# clone_Schematics.net
KiCad netlist of a schematic drawn in Altium Designer
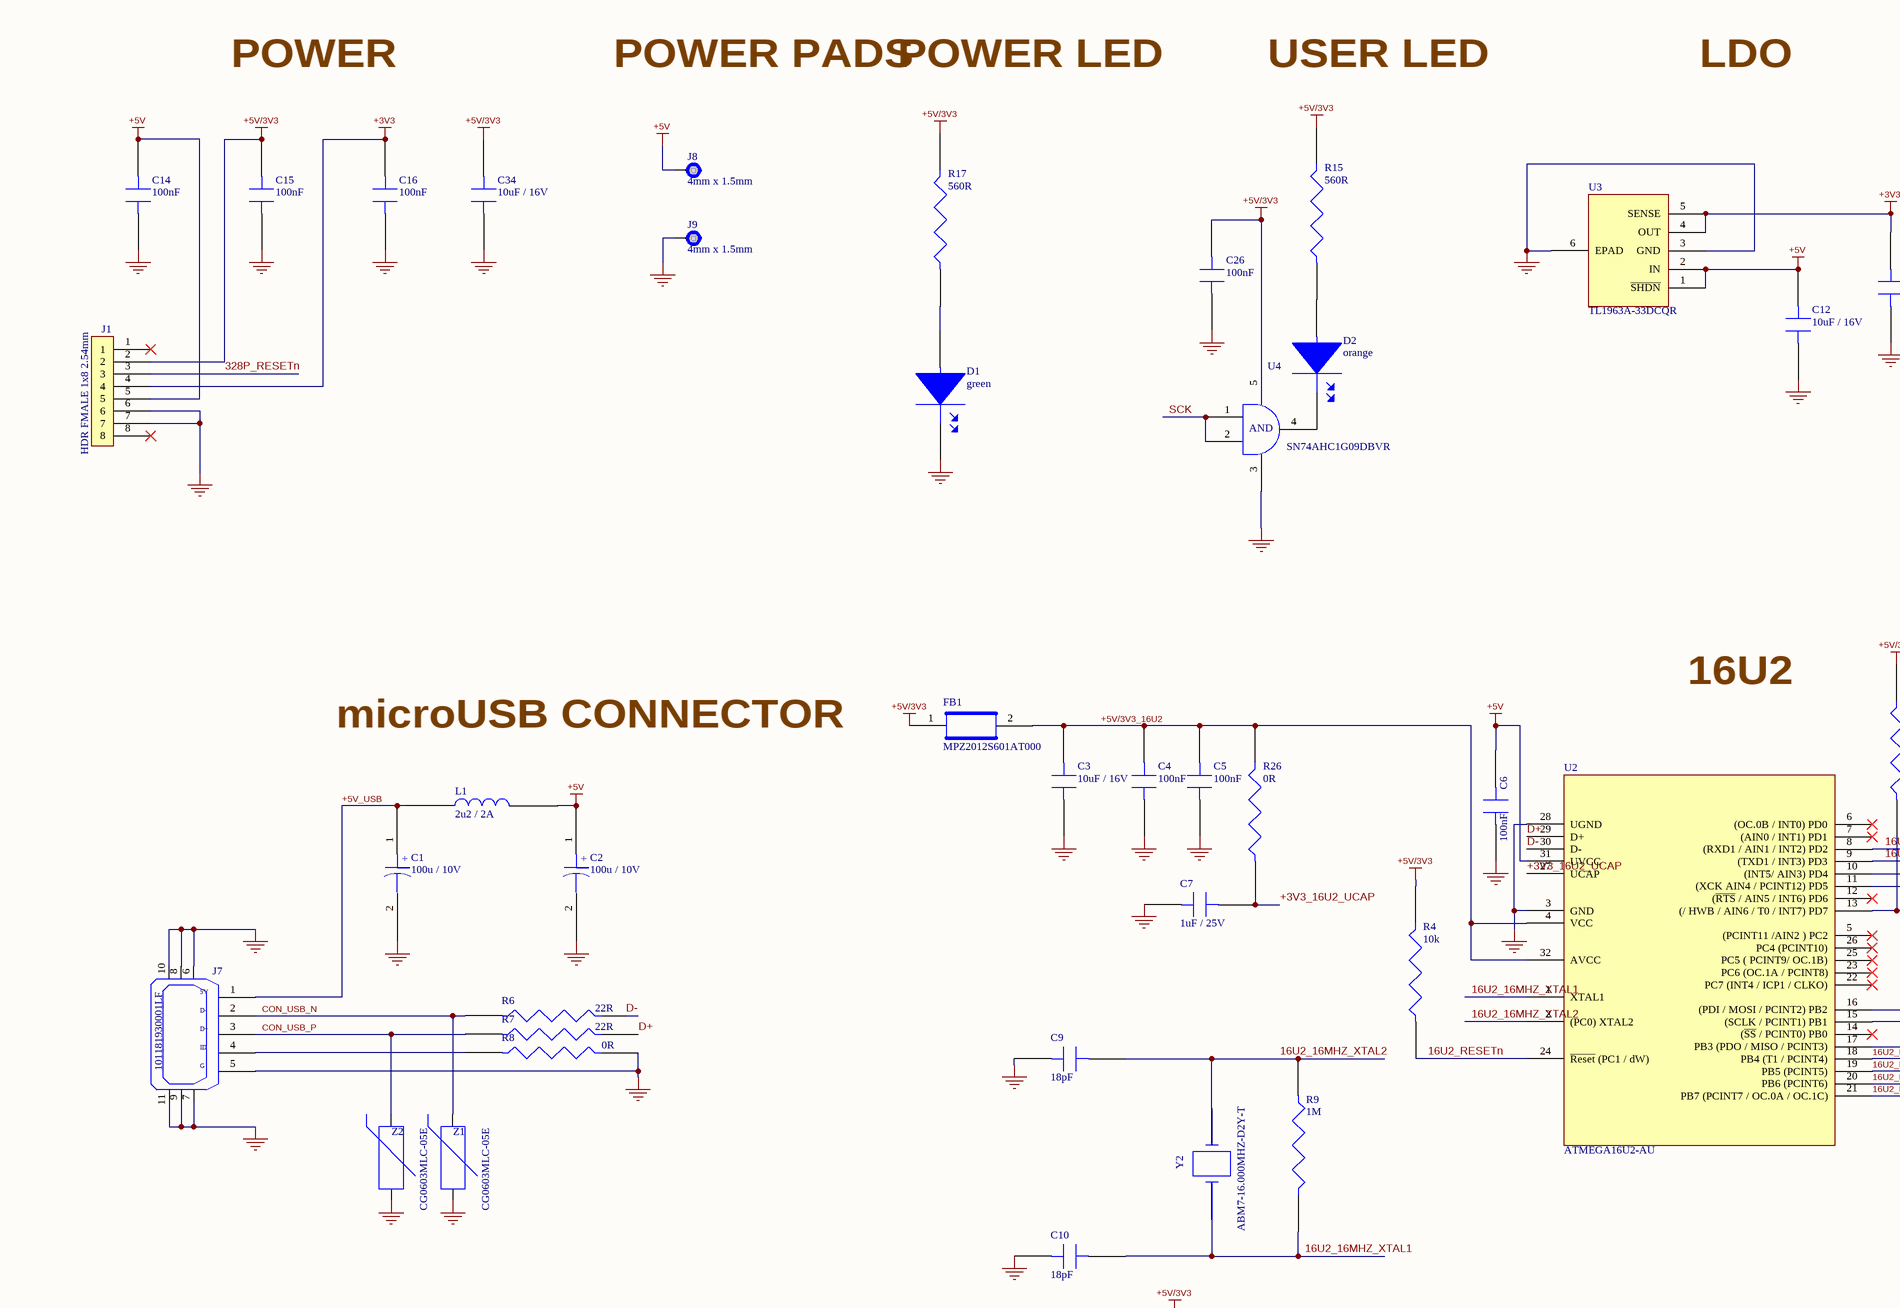
[diagram p0: clone_Schematics.SchDoc, top left]
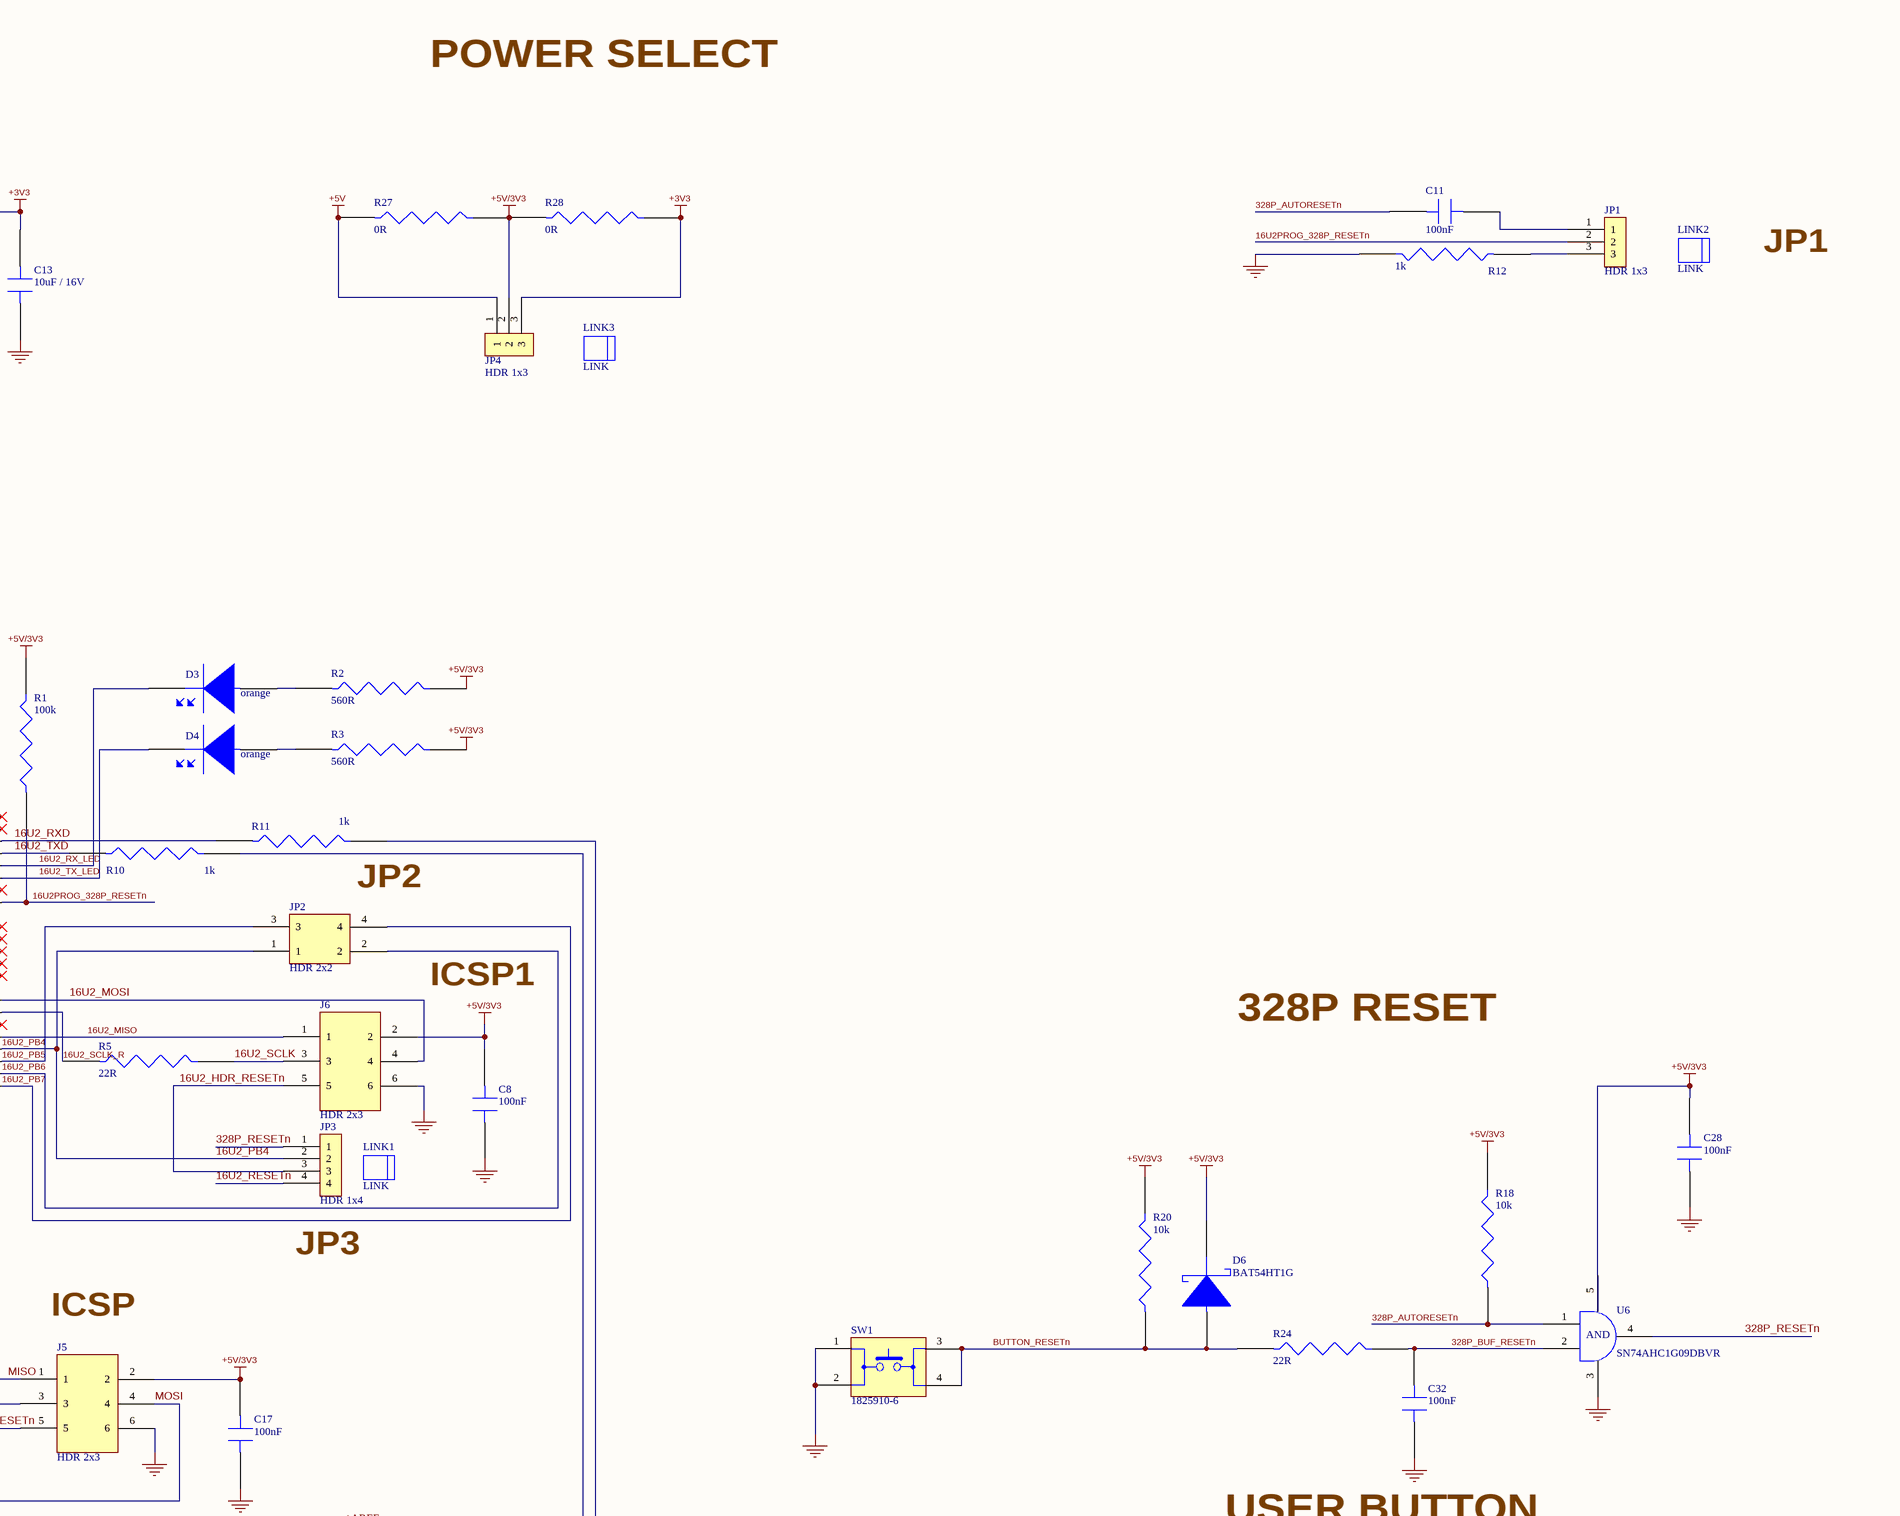
[diagram p1: clone_Schematics.SchDoc, top right]
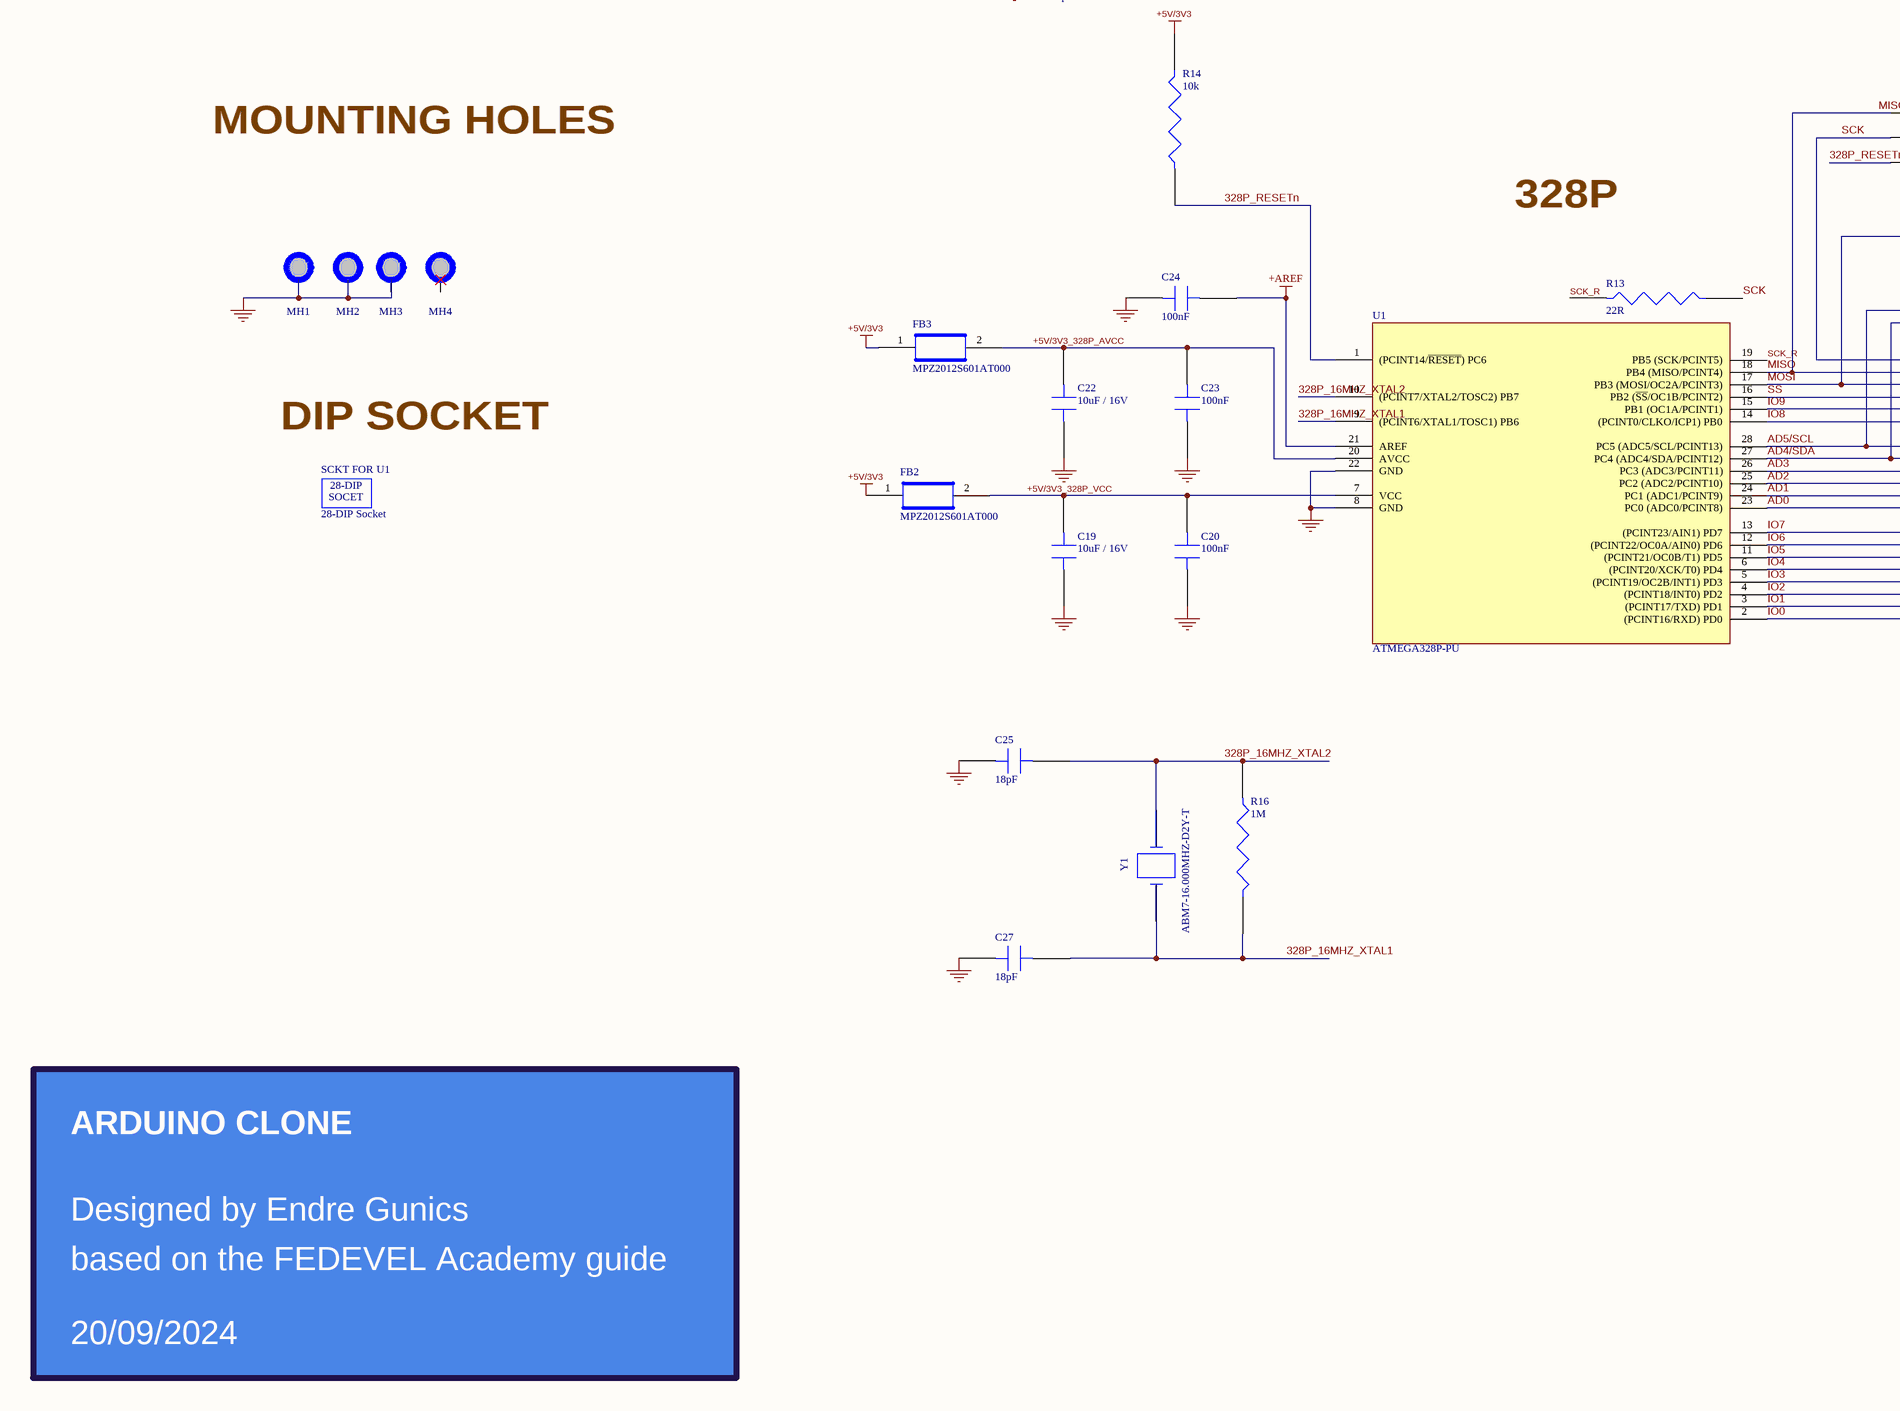
[diagram p2: clone_Schematics.SchDoc, bottom left]
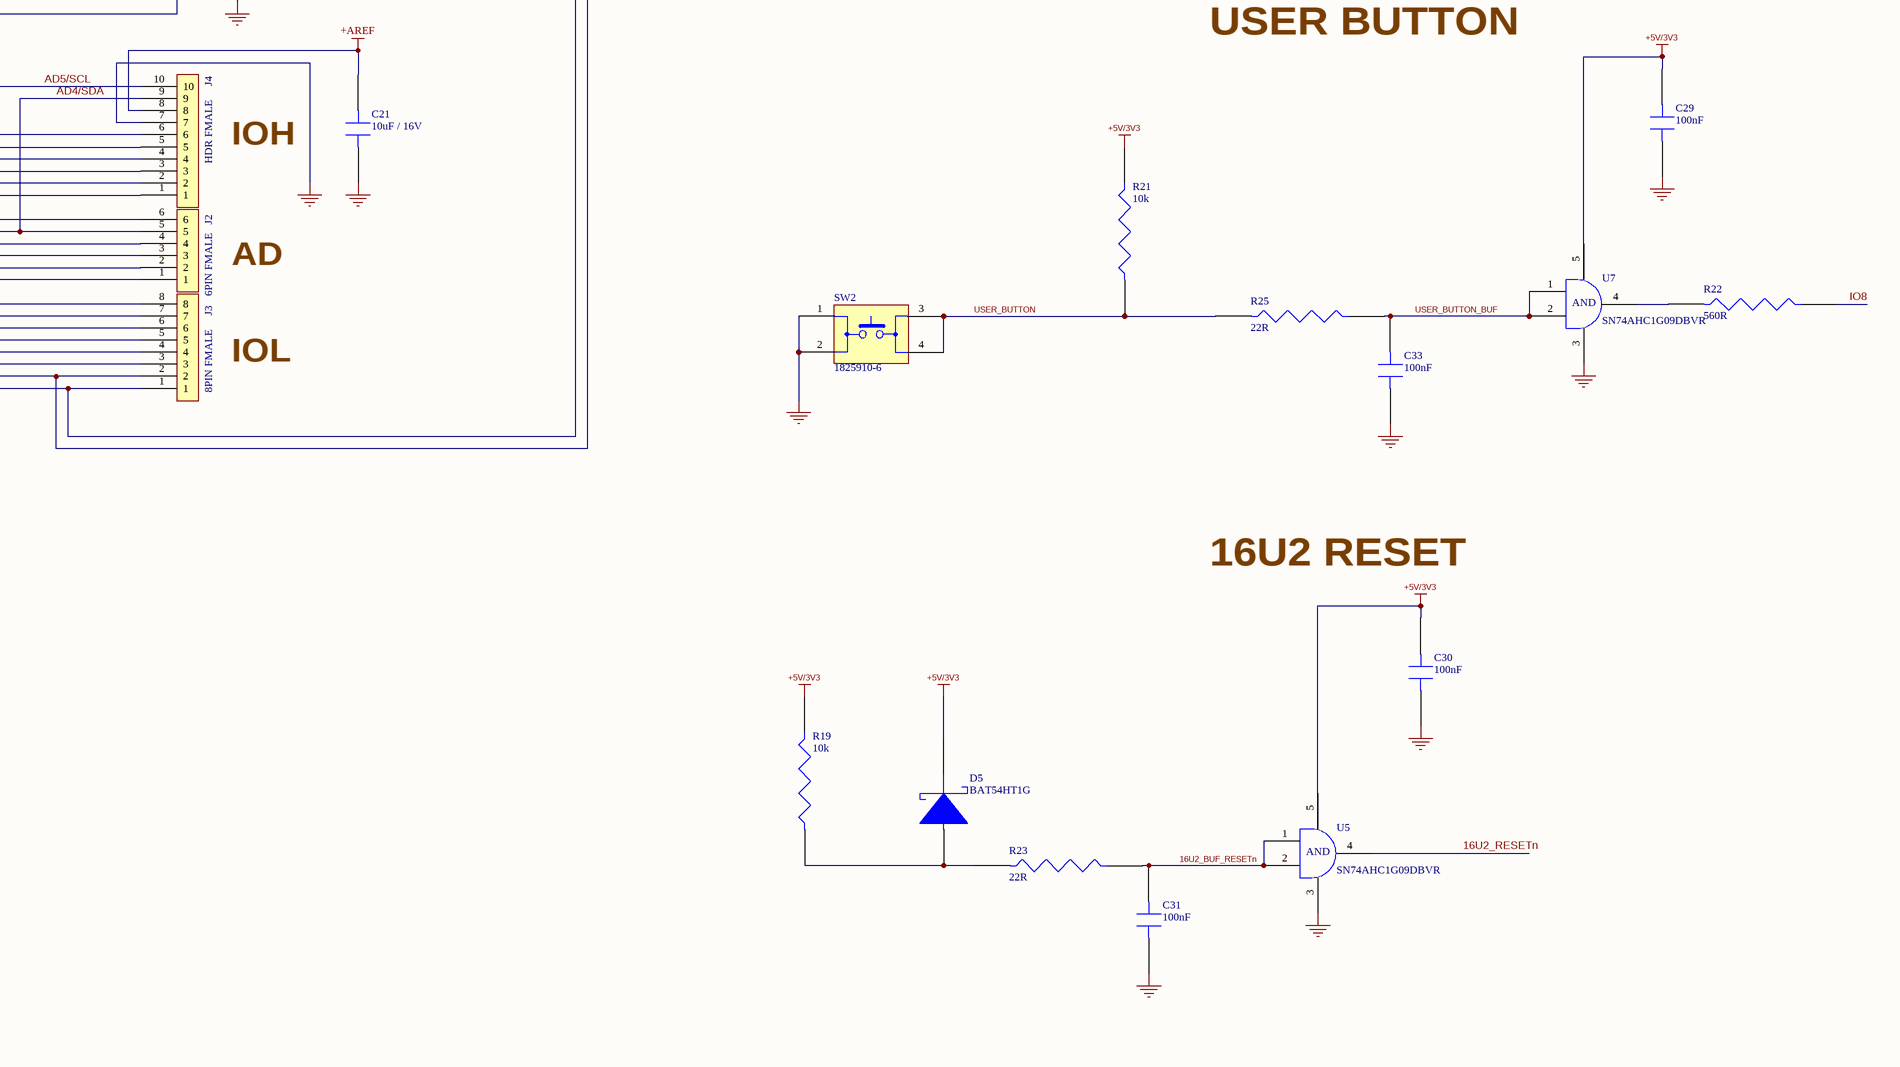
[diagram p3: clone_Schematics.SchDoc, bottom right]

(export (version "E")
  (design (tool "Eeschema 10.0.6"))
  (components
    (comp (ref "C1")
      (value "100u / 10V")
      (footprint "C_ALU")
      (description "Aluminum Electrolytic Capacitor, 100 uF, 10 V, ± 20%, 1000 hours @ 85°C, Radial Can - SMD")
      (fields
        (field (name "MANUFACTURER") "Panasonic")
        (field (name "MANUFACTURER PART NUMBER") "EEE-1AA101WR")
      )
      (libsource (lib "clone_Schematic_libary") (part "EEE-1AA101WR"))
    )
    (comp (ref "C2")
      (value "100u / 10V")
      (footprint "C_ALU")
      (description "Aluminum Electrolytic Capacitor, 100 uF, 10 V, ± 20%, 1000 hours @ 85°C, Radial Can - SMD")
      (fields
        (field (name "MANUFACTURER") "Panasonic")
        (field (name "MANUFACTURER PART NUMBER") "EEE-1AA101WR")
      )
      (libsource (lib "clone_Schematic_libary") (part "EEE-1AA101WR"))
    )
    (comp (ref "C3")
      (value "10uF / 16V")
      (footprint "C0805")
      (libsource (lib "clone_Schematic_libary") (part "CAP2"))
    )
    (comp (ref "C4")
      (value "100nF")
      (footprint "C0805")
      (description "Multilayer Ceramic Capacitor, 0.1 uF, 50 V, ± 10%, X7R, 0805 [2012 Metric]")
      (fields
        (field (name "MANUFACTURER") "TDK")
        (field (name "MANUFACTURER PART NUMBER") "C2012X7R1H104K085AA")
      )
      (libsource (lib "clone_Schematic_libary") (part "C2012X7R1H104K085AA"))
    )
    (comp (ref "C5")
      (value "100nF")
      (footprint "C0805")
      (description "Multilayer Ceramic Capacitor, 0.1 uF, 50 V, ± 10%, X7R, 0805 [2012 Metric]")
      (fields
        (field (name "MANUFACTURER") "TDK")
        (field (name "MANUFACTURER PART NUMBER") "C2012X7R1H104K085AA")
      )
      (libsource (lib "clone_Schematic_libary") (part "C2012X7R1H104K085AA"))
    )
    (comp (ref "C6")
      (value "100nF")
      (footprint "C0805")
      (description "Multilayer Ceramic Capacitor, 0.1 uF, 50 V, ± 10%, X7R, 0805 [2012 Metric]")
      (fields
        (field (name "MANUFACTURER") "TDK")
        (field (name "MANUFACTURER PART NUMBER") "C2012X7R1H104K085AA")
      )
      (libsource (lib "clone_Schematic_libary") (part "C2012X7R1H104K085AA"))
    )
    (comp (ref "C7")
      (value "1uF / 25V")
      (footprint "C0805")
      (description "CAP CER 1UF 25V X5R 0805")
      (fields
        (field (name "MANUFACTURER") "TDK")
        (field (name "MANUFACTURER PART NUMBER") "C2012X5R1E105K125AA")
      )
      (libsource (lib "clone_Schematic_libary") (part "C2012X5R1E105K125AA"))
    )
    (comp (ref "C8")
      (value "100nF")
      (footprint "C0805")
      (description "Multilayer Ceramic Capacitor, 0.1 uF, 50 V, ± 10%, X7R, 0805 [2012 Metric]")
      (fields
        (field (name "MANUFACTURER") "TDK")
        (field (name "MANUFACTURER PART NUMBER") "C2012X7R1H104K085AA")
      )
      (libsource (lib "clone_Schematic_libary") (part "C2012X7R1H104K085AA"))
    )
    (comp (ref "C9")
      (value "18pF")
      (footprint "C0805")
      (description "Cap Cer 0805 18PF 50VDC X8G 5%")
      (fields
        (field (name "MANUFACTURER") "KEMET")
        (field (name "MANUFACTURER PART NUMBER") "C0805C180J5TACTU")
      )
      (libsource (lib "clone_Schematic_libary") (part "C0805C180J5TACTU"))
    )
    (comp (ref "C10")
      (value "18pF")
      (footprint "C0805")
      (description "Cap Cer 0805 18PF 50VDC X8G 5%")
      (fields
        (field (name "MANUFACTURER") "KEMET")
        (field (name "MANUFACTURER PART NUMBER") "C0805C180J5TACTU")
      )
      (libsource (lib "clone_Schematic_libary") (part "C0805C180J5TACTU"))
    )
    (comp (ref "C11")
      (value "100nF")
      (footprint "C0805")
      (description "Multilayer Ceramic Capacitor, 0.1 uF, 50 V, ± 10%, X7R, 0805 [2012 Metric]")
      (fields
        (field (name "MANUFACTURER") "TDK")
        (field (name "MANUFACTURER PART NUMBER") "C2012X7R1H104K085AA")
      )
      (libsource (lib "clone_Schematic_libary") (part "C2012X7R1H104K085AA"))
    )
    (comp (ref "C12")
      (value "10uF / 16V")
      (footprint "C0805")
      (libsource (lib "clone_Schematic_libary") (part "CAP2"))
    )
    (comp (ref "C13")
      (value "10uF / 16V")
      (footprint "C0805")
      (libsource (lib "clone_Schematic_libary") (part "CAP2"))
    )
    (comp (ref "C14")
      (value "100nF")
      (footprint "C0805")
      (description "Multilayer Ceramic Capacitor, 0.1 uF, 50 V, ± 10%, X7R, 0805 [2012 Metric]")
      (fields
        (field (name "MANUFACTURER") "TDK")
        (field (name "MANUFACTURER PART NUMBER") "C2012X7R1H104K085AA")
      )
      (libsource (lib "clone_Schematic_libary") (part "C2012X7R1H104K085AA"))
    )
    (comp (ref "C15")
      (value "100nF")
      (footprint "C0805")
      (description "Multilayer Ceramic Capacitor, 0.1 uF, 50 V, ± 10%, X7R, 0805 [2012 Metric]")
      (fields
        (field (name "MANUFACTURER") "TDK")
        (field (name "MANUFACTURER PART NUMBER") "C2012X7R1H104K085AA")
      )
      (libsource (lib "clone_Schematic_libary") (part "C2012X7R1H104K085AA"))
    )
    (comp (ref "C16")
      (value "100nF")
      (footprint "C0805")
      (description "Multilayer Ceramic Capacitor, 0.1 uF, 50 V, ± 10%, X7R, 0805 [2012 Metric]")
      (fields
        (field (name "MANUFACTURER") "TDK")
        (field (name "MANUFACTURER PART NUMBER") "C2012X7R1H104K085AA")
      )
      (libsource (lib "clone_Schematic_libary") (part "C2012X7R1H104K085AA"))
    )
    (comp (ref "C17")
      (value "100nF")
      (footprint "C0805")
      (description "Multilayer Ceramic Capacitor, 0.1 uF, 50 V, ± 10%, X7R, 0805 [2012 Metric]")
      (fields
        (field (name "MANUFACTURER") "TDK")
        (field (name "MANUFACTURER PART NUMBER") "C2012X7R1H104K085AA")
      )
      (libsource (lib "clone_Schematic_libary") (part "C2012X7R1H104K085AA"))
    )
    (comp (ref "C19")
      (value "10uF / 16V")
      (footprint "C0805")
      (libsource (lib "clone_Schematic_libary") (part "CAP2"))
    )
    (comp (ref "C20")
      (value "100nF")
      (footprint "C0805")
      (description "Multilayer Ceramic Capacitor, 0.1 uF, 50 V, ± 10%, X7R, 0805 [2012 Metric]")
      (fields
        (field (name "MANUFACTURER") "TDK")
        (field (name "MANUFACTURER PART NUMBER") "C2012X7R1H104K085AA")
      )
      (libsource (lib "clone_Schematic_libary") (part "C2012X7R1H104K085AA"))
    )
    (comp (ref "C21")
      (value "10uF / 16V")
      (footprint "C0805")
      (libsource (lib "clone_Schematic_libary") (part "CAP2"))
    )
    (comp (ref "C22")
      (value "10uF / 16V")
      (footprint "C0805")
      (libsource (lib "clone_Schematic_libary") (part "CAP2"))
    )
    (comp (ref "C23")
      (value "100nF")
      (footprint "C0805")
      (description "Multilayer Ceramic Capacitor, 0.1 uF, 50 V, ± 10%, X7R, 0805 [2012 Metric]")
      (fields
        (field (name "MANUFACTURER") "TDK")
        (field (name "MANUFACTURER PART NUMBER") "C2012X7R1H104K085AA")
      )
      (libsource (lib "clone_Schematic_libary") (part "C2012X7R1H104K085AA"))
    )
    (comp (ref "C24")
      (value "100nF")
      (footprint "C0805")
      (description "Multilayer Ceramic Capacitor, 0.1 uF, 50 V, ± 10%, X7R, 0805 [2012 Metric]")
      (fields
        (field (name "MANUFACTURER") "TDK")
        (field (name "MANUFACTURER PART NUMBER") "C2012X7R1H104K085AA")
      )
      (libsource (lib "clone_Schematic_libary") (part "C2012X7R1H104K085AA"))
    )
    (comp (ref "C25")
      (value "18pF")
      (footprint "C0805")
      (description "Cap Cer 0805 18PF 50VDC X8G 5%")
      (fields
        (field (name "MANUFACTURER") "KEMET")
        (field (name "MANUFACTURER PART NUMBER") "C0805C180J5TACTU")
      )
      (libsource (lib "clone_Schematic_libary") (part "C0805C180J5TACTU"))
    )
    (comp (ref "C26")
      (value "100nF")
      (footprint "C0805")
      (description "Multilayer Ceramic Capacitor, 0.1 uF, 50 V, ± 10%, X7R, 0805 [2012 Metric]")
      (fields
        (field (name "MANUFACTURER") "TDK")
        (field (name "MANUFACTURER PART NUMBER") "C2012X7R1H104K085AA")
      )
      (libsource (lib "clone_Schematic_libary") (part "C2012X7R1H104K085AA"))
    )
    (comp (ref "C27")
      (value "18pF")
      (footprint "C0805")
      (description "Cap Cer 0805 18PF 50VDC X8G 5%")
      (fields
        (field (name "MANUFACTURER") "KEMET")
        (field (name "MANUFACTURER PART NUMBER") "C0805C180J5TACTU")
      )
      (libsource (lib "clone_Schematic_libary") (part "C0805C180J5TACTU"))
    )
    (comp (ref "C28")
      (value "100nF")
      (footprint "C0805")
      (description "Multilayer Ceramic Capacitor, 0.1 uF, 50 V, ± 10%, X7R, 0805 [2012 Metric]")
      (fields
        (field (name "MANUFACTURER") "TDK")
        (field (name "MANUFACTURER PART NUMBER") "C2012X7R1H104K085AA")
      )
      (libsource (lib "clone_Schematic_libary") (part "C2012X7R1H104K085AA"))
    )
    (comp (ref "C29")
      (value "100nF")
      (footprint "C0805")
      (description "Multilayer Ceramic Capacitor, 0.1 uF, 50 V, ± 10%, X7R, 0805 [2012 Metric]")
      (fields
        (field (name "MANUFACTURER") "TDK")
        (field (name "MANUFACTURER PART NUMBER") "C2012X7R1H104K085AA")
      )
      (libsource (lib "clone_Schematic_libary") (part "C2012X7R1H104K085AA"))
    )
    (comp (ref "C30")
      (value "100nF")
      (footprint "C0805")
      (description "Multilayer Ceramic Capacitor, 0.1 uF, 50 V, ± 10%, X7R, 0805 [2012 Metric]")
      (fields
        (field (name "MANUFACTURER") "TDK")
        (field (name "MANUFACTURER PART NUMBER") "C2012X7R1H104K085AA")
      )
      (libsource (lib "clone_Schematic_libary") (part "C2012X7R1H104K085AA"))
    )
    (comp (ref "C31")
      (value "100nF")
      (footprint "C0805")
      (description "Multilayer Ceramic Capacitor, 0.1 uF, 50 V, ± 10%, X7R, 0805 [2012 Metric]")
      (fields
        (field (name "MANUFACTURER") "TDK")
        (field (name "MANUFACTURER PART NUMBER") "C2012X7R1H104K085AA")
      )
      (libsource (lib "clone_Schematic_libary") (part "C2012X7R1H104K085AA"))
    )
    (comp (ref "C32")
      (value "100nF")
      (footprint "C0805")
      (description "Multilayer Ceramic Capacitor, 0.1 uF, 50 V, ± 10%, X7R, 0805 [2012 Metric]")
      (fields
        (field (name "MANUFACTURER") "TDK")
        (field (name "MANUFACTURER PART NUMBER") "C2012X7R1H104K085AA")
      )
      (libsource (lib "clone_Schematic_libary") (part "C2012X7R1H104K085AA"))
    )
    (comp (ref "C33")
      (value "100nF")
      (footprint "C0805")
      (description "Multilayer Ceramic Capacitor, 0.1 uF, 50 V, ± 10%, X7R, 0805 [2012 Metric]")
      (fields
        (field (name "MANUFACTURER") "TDK")
        (field (name "MANUFACTURER PART NUMBER") "C2012X7R1H104K085AA")
      )
      (libsource (lib "clone_Schematic_libary") (part "C2012X7R1H104K085AA"))
    )
    (comp (ref "C34")
      (value "10uF / 16V")
      (footprint "C0805")
      (libsource (lib "clone_Schematic_libary") (part "CAP2"))
    )
    (comp (ref "D1")
      (value "green")
      (footprint "orangeDiode")
      (description "LED Uni-Color Green 572nm Automotive 2-Pin Chip 0603(1608Metric) T/R")
      (fields
        (field (name "MANUFACTURER") "Osram Opto")
        (field (name "MANUFACTURER PART NUMBER") "LGL29K-G2J1-24-Z")
      )
      (libsource (lib "clone_Schematic_libary") (part "LGL29K-G2J1-24-Z"))
    )
    (comp (ref "D2")
      (value "orange")
      (footprint "orangeDiode")
      (libsource (lib "clone_Schematic_libary") (part "LED"))
    )
    (comp (ref "D3")
      (value "orange")
      (footprint "orangeDiode")
      (libsource (lib "clone_Schematic_libary") (part "LED"))
    )
    (comp (ref "D4")
      (value "orange")
      (footprint "orangeDiode")
      (libsource (lib "clone_Schematic_libary") (part "LED"))
    )
    (comp (ref "D5")
      (value "BAT54HT1G")
      (footprint "SOD323")
      (description "Small Signal Schottky Diode, Single, 30 V, 200 Ma, 800 Mv, 600 Ma, 150 C")
      (fields (field (name "MANUFACTURER") "ON Semiconductor / Fairchild"))
      (libsource (lib "clone_Schematic_libary") (part "BAT54HT1G"))
    )
    (comp (ref "D6")
      (value "BAT54HT1G")
      (footprint "SOD323")
      (description "Small Signal Schottky Diode, Single, 30 V, 200 Ma, 800 Mv, 600 Ma, 150 C")
      (fields (field (name "MANUFACTURER") "ON Semiconductor / Fairchild"))
      (libsource (lib "clone_Schematic_libary") (part "BAT54HT1G"))
    )
    (comp (ref "FB1")
      (value "MPZ2012S601AT000")
      (footprint "C0805")
      (description "Ferrite Beads Multi-Layer Power 600Ohm 25% 100MHz 2A 100mOhm DCR 0805 T/R")
      (fields (field (name "MANUFACTURER") "TDK") (field (name "TOLERANCE") "25%"))
      (libsource (lib "clone_Schematic_libary") (part "MPZ2012S601AT000"))
    )
    (comp (ref "FB2")
      (value "MPZ2012S601AT000")
      (footprint "C0805")
      (description "Ferrite Beads Multi-Layer Power 600Ohm 25% 100MHz 2A 100mOhm DCR 0805 T/R")
      (fields (field (name "MANUFACTURER") "TDK") (field (name "TOLERANCE") "25%"))
      (libsource (lib "clone_Schematic_libary") (part "MPZ2012S601AT000"))
    )
    (comp (ref "FB3")
      (value "MPZ2012S601AT000")
      (footprint "C0805")
      (description "Ferrite Beads Multi-Layer Power 600Ohm 25% 100MHz 2A 100mOhm DCR 0805 T/R")
      (fields (field (name "MANUFACTURER") "TDK") (field (name "TOLERANCE") "25%"))
      (libsource (lib "clone_Schematic_libary") (part "MPZ2012S601AT000"))
    )
    (comp (ref "J1")
      (value "HDR FMALE 1x8 2.54mm")
      (footprint "8PINFMALE")
      (libsource (lib "clone_Schematic_libary") (part "8PIN"))
    )
    (comp (ref "J2")
      (value "6PIN FMALE")
      (footprint "6PINFMALE")
      (libsource (lib "clone_Schematic_libary") (part "6PIN"))
    )
    (comp (ref "J3") (value "8PIN FMALE") (footprint "8PINFMALE") (libsource (lib "") (part "8PIN_1")))
    (comp (ref "J4")
      (value "HDR FMALE")
      (footprint "10PINFMALE")
      (libsource (lib "clone_Schematic_libary") (part "10PIN"))
    )
    (comp (ref "J5")
      (value "HDR 2x3")
      (footprint "HDR 2x3")
      (description "Conn Unshrouded Header HDR 6 POS 2.54mm Solder ST Top Entry Thru-Hole BergStik® Bulk")
      (fields
        (field (name "MANUFACTURER") "Amphenol ICC / FCI")
        (field (name "MANUFACTURER PART NUMBER") "67997-106HLF")
      )
      (libsource (lib "clone_Schematic_libary") (part "67997-106HLF"))
    )
    (comp (ref "J6")
      (value "HDR 2x3")
      (footprint "HDR 2x3")
      (description "Conn Unshrouded Header HDR 6 POS 2.54mm Solder ST Top Entry Thru-Hole BergStik® Bulk")
      (fields
        (field (name "MANUFACTURER") "Amphenol ICC / FCI")
        (field (name "MANUFACTURER PART NUMBER") "67997-106HLF")
      )
      (libsource (lib "clone_Schematic_libary") (part "67997-106HLF"))
    )
    (comp (ref "J7")
      (value "101181930001LF")
      (footprint "USBmicro")
      (description "MICRO USB B0TYPE F-10118193-0001LF ¦ Amphenol FCI (Amphenol CS) 101181930001LF")
      (fields (field (name "MANUFACTURER") "Amphenol Communications Solutions"))
      (libsource (lib "clone_Schematic_libary") (part "101181930001LF"))
    )
    (comp (ref "J8")
      (value "4mm x 1.5mm")
      (footprint "PAD WITH HOLE")
      (description "pad with hole")
      (libsource (lib "clone_Schematic_libary") (part "PAD_WITH_HOLE"))
    )
    (comp (ref "J9")
      (value "4mm x 1.5mm")
      (footprint "PAD WITH HOLE")
      (description "pad with hole")
      (libsource (lib "clone_Schematic_libary") (part "PAD_WITH_HOLE"))
    )
    (comp (ref "JP1")
      (value "HDR 1x3")
      (footprint "HDR 1x3")
      (description "Conn Unshrouded Header HDR 3 POS 2.54mm Solder ST Top Entry Thru-Hole BergStik® Automotive Bulk")
      (fields
        (field (name "MANUFACTURER") "Amphenol ICC / FCI")
        (field (name "MANUFACTURER PART NUMBER") "68000-103HLF")
      )
      (libsource (lib "") (part "68000-103HLF_1"))
    )
    (comp (ref "JP2")
      (value "HDR 2x2")
      (footprint "HDR 2x2")
      (description "Conn Unshrouded Header HDR 4 POS 2.54mm Solder ST Top Entry Thru-Hole BergStik® Bulk")
      (fields
        (field (name "MANUFACTURER") "Amphenol ICC / FCI")
        (field (name "MANUFACTURER PART NUMBER") "68602-204HLF")
      )
      (libsource (lib "clone_Schematic_libary") (part "68602-204HLF"))
    )
    (comp (ref "JP3")
      (value "HDR 1x4")
      (footprint "HDR 1x4")
      (description "Conn Unshrouded Header HDR 4 POS 2.54mm Solder ST Thru-Hole Bag")
      (fields
        (field (name "MANUFACTURER") "Amphenol ICC / FCI")
        (field (name "MANUFACTURER PART NUMBER") "68001-204HLF")
      )
      (libsource (lib "clone_Schematic_libary") (part "68001-204HLF"))
    )
    (comp (ref "JP4")
      (value "HDR 1x3")
      (footprint "HDR 1x3")
      (description "Conn Unshrouded Header HDR 3 POS 2.54mm Solder ST Top Entry Thru-Hole BergStik® Automotive Bulk")
      (fields
        (field (name "MANUFACTURER") "Amphenol ICC / FCI")
        (field (name "MANUFACTURER PART NUMBER") "68000-103HLF")
      )
      (libsource (lib "clone_Schematic_libary") (part "68000-103HLF"))
    )
    (comp (ref "L1")
      (value "2u2 / 2A")
      (footprint "InductorC120")
      (libsource (lib "clone_Schematic_libary") (part "inductor"))
    )
    (comp (ref "LINK1")
      (value "LINK")
      (description "2 Position 2.54 mm Centerline Single Circuit Open Top Jumper")
      (fields
        (field (name "MANUFACTURER") "Sullins")
        (field (name "MANUFACTURER PART NUMBER") "QPC02SXGN-RC")
      )
      (libsource (lib "clone_Schematic_libary") (part "QPC02SXGN-RC"))
    )
    (comp (ref "LINK2")
      (value "LINK")
      (description "2 Position 2.54 mm Centerline Single Circuit Open Top Jumper")
      (fields
        (field (name "MANUFACTURER") "Sullins")
        (field (name "MANUFACTURER PART NUMBER") "QPC02SXGN-RC")
      )
      (libsource (lib "clone_Schematic_libary") (part "QPC02SXGN-RC"))
    )
    (comp (ref "LINK3")
      (value "LINK")
      (description "2 Position 2.54 mm Centerline Single Circuit Open Top Jumper")
      (fields
        (field (name "MANUFACTURER") "Sullins")
        (field (name "MANUFACTURER PART NUMBER") "QPC02SXGN-RC")
      )
      (libsource (lib "clone_Schematic_libary") (part "QPC02SXGN-RC"))
    )
    (comp (ref "MH1")
      (value "MH_7.4MMC_3.2mmD")
      (footprint "MH_7.4_MMD_3.2_MMD")
      (description "MH 7.4 mm Dia 3.2mm Drill")
      (libsource (lib "clone_Schematic_libary") (part "mounting hole 7.4mm C3.2"))
    )
    (comp (ref "MH2")
      (value "MH_7.4MMC_3.2mmD")
      (footprint "MH_7.4_MMD_3.2_MMD")
      (description "MH 7.4 mm Dia 3.2mm Drill")
      (libsource (lib "clone_Schematic_libary") (part "mounting hole 7.4mm C3.2"))
    )
    (comp (ref "MH3")
      (value "MH_7.4MMC_3.2mmD")
      (footprint "MH_7.4_MMD_3.2_MMD")
      (description "MH 7.4 mm Dia 3.2mm Drill")
      (libsource (lib "clone_Schematic_libary") (part "mounting hole 7.4mm C3.2"))
    )
    (comp (ref "MH4")
      (value "mounting hole nonplated")
      (footprint "MH_NOPLATE")
      (description "mounting hole nonplated 7.4x3.2 non copper")
      (libsource (lib "clone_Schematic_libary") (part "mounting hole nonplated"))
    )
    (comp (ref "R1")
      (value "100k")
      (footprint "R0805")
      (description "SMD Chip Resistor, 100 kOhm, ï¿½ 5%, 125 mW, 0805 [2012 Metric], Thick Film, General Purpose")
      (fields
        (field (name "MANUFACTURER") "Yageo")
        (field (name "MANUFACTURER PART NUMBER") "RC0805JR-07100KL")
      )
      (libsource (lib "clone_Schematic_libary") (part "RC0805JR-07100KL"))
    )
    (comp (ref "R2")
      (value "560R")
      (footprint "R0805")
      (description "Res General Purpose Thick Film 0805 560 Ohm 1% 1/8W ±100ppm/°C Molded Paper T/R")
      (fields
        (field (name "MANUFACTURER") "Yageo")
        (field (name "MANUFACTURER PART NUMBER") "RC0805FR-07560RL")
      )
      (libsource (lib "clone_Schematic_libary") (part "RC0805FR-07560RL"))
    )
    (comp (ref "R3")
      (value "560R")
      (footprint "R0805")
      (description "Res General Purpose Thick Film 0805 560 Ohm 1% 1/8W ±100ppm/°C Molded Paper T/R")
      (fields
        (field (name "MANUFACTURER") "Yageo")
        (field (name "MANUFACTURER PART NUMBER") "RC0805FR-07560RL")
      )
      (libsource (lib "clone_Schematic_libary") (part "RC0805FR-07560RL"))
    )
    (comp (ref "R4")
      (value "10k")
      (footprint "R0805")
      (description "SMD Chip Resistor, 10 kOhm, ï¿½ 1%, 125 mW, 0805 [2012 Metric], Thick Film, General Purpose")
      (fields
        (field (name "MANUFACTURER") "Yageo")
        (field (name "MANUFACTURER PART NUMBER") "RC0805FR-0710KL")
      )
      (libsource (lib "clone_Schematic_libary") (part "RC0805FR-0710KL"))
    )
    (comp (ref "R5")
      (value "22R")
      (footprint "R0805")
      (description "SMD Chip Resistor, 22 Ohm, ± 1%, 125 mW, 0805 [2012 Metric], Thick Film, General Purpose")
      (fields
        (field (name "MANUFACTURER") "Yageo")
        (field (name "MANUFACTURER PART NUMBER") "RC0805FR-0722RL")
      )
      (libsource (lib "clone_Schematic_libary") (part "RC0805FR-0722RL"))
    )
    (comp (ref "R6")
      (value "22R")
      (footprint "R0805")
      (description "SMD Chip Resistor, 22 Ohm, ± 1%, 125 mW, 0805 [2012 Metric], Thick Film, General Purpose")
      (fields
        (field (name "MANUFACTURER") "Yageo")
        (field (name "MANUFACTURER PART NUMBER") "RC0805FR-0722RL")
      )
      (libsource (lib "clone_Schematic_libary") (part "RC0805FR-0722RL"))
    )
    (comp (ref "R7")
      (value "22R")
      (footprint "R0805")
      (description "SMD Chip Resistor, 22 Ohm, ± 1%, 125 mW, 0805 [2012 Metric], Thick Film, General Purpose")
      (fields
        (field (name "MANUFACTURER") "Yageo")
        (field (name "MANUFACTURER PART NUMBER") "RC0805FR-0722RL")
      )
      (libsource (lib "clone_Schematic_libary") (part "RC0805FR-0722RL"))
    )
    (comp (ref "R8")
      (value "0R")
      (footprint "R0805")
      (libsource (lib "clone_Schematic_libary") (part "0Ohm Resistor"))
    )
    (comp (ref "R9")
      (value "1M")
      (footprint "R0805")
      (description "SMD Chip Resistor, 1 MOhm, ï¿½ 1%, 125 mW, 0805 [2012 Metric], Thick Film, General Purpose")
      (fields
        (field (name "MANUFACTURER") "Yageo")
        (field (name "MANUFACTURER PART NUMBER") "RC0805FR-071ML")
      )
      (libsource (lib "clone_Schematic_libary") (part "RC0805FR-071ML"))
    )
    (comp (ref "R10")
      (value "1k")
      (footprint "R0805")
      (description "SMD Chip Resistor, 1 kOhm, ï¿½ 1%, 125 mW, 0805 [2012 Metric], Thick Film, General Purpose")
      (fields
        (field (name "MANUFACTURER") "Yageo")
        (field (name "MANUFACTURER PART NUMBER") "RC0805FR-071KL")
      )
      (libsource (lib "clone_Schematic_libary") (part "RC0805FR-071KL"))
    )
    (comp (ref "R11")
      (value "1k")
      (footprint "R0805")
      (description "SMD Chip Resistor, 1 kOhm, ï¿½ 1%, 125 mW, 0805 [2012 Metric], Thick Film, General Purpose")
      (fields
        (field (name "MANUFACTURER") "Yageo")
        (field (name "MANUFACTURER PART NUMBER") "RC0805FR-071KL")
      )
      (libsource (lib "clone_Schematic_libary") (part "RC0805FR-071KL"))
    )
    (comp (ref "R12")
      (value "1k")
      (footprint "R0805")
      (description "SMD Chip Resistor, 1 kOhm, ï¿½ 1%, 125 mW, 0805 [2012 Metric], Thick Film, General Purpose")
      (fields
        (field (name "MANUFACTURER") "Yageo")
        (field (name "MANUFACTURER PART NUMBER") "RC0805FR-071KL")
      )
      (libsource (lib "clone_Schematic_libary") (part "RC0805FR-071KL"))
    )
    (comp (ref "R13")
      (value "22R")
      (footprint "R0805")
      (description "SMD Chip Resistor, 22 Ohm, ± 1%, 125 mW, 0805 [2012 Metric], Thick Film, General Purpose")
      (fields
        (field (name "MANUFACTURER") "Yageo")
        (field (name "MANUFACTURER PART NUMBER") "RC0805FR-0722RL")
      )
      (libsource (lib "clone_Schematic_libary") (part "RC0805FR-0722RL"))
    )
    (comp (ref "R14")
      (value "10k")
      (footprint "R0805")
      (description "SMD Chip Resistor, 10 kOhm, ï¿½ 1%, 125 mW, 0805 [2012 Metric], Thick Film, General Purpose")
      (fields
        (field (name "MANUFACTURER") "Yageo")
        (field (name "MANUFACTURER PART NUMBER") "RC0805FR-0710KL")
      )
      (libsource (lib "clone_Schematic_libary") (part "RC0805FR-0710KL"))
    )
    (comp (ref "R15")
      (value "560R")
      (footprint "R0805")
      (description "Res General Purpose Thick Film 0805 560 Ohm 1% 1/8W ±100ppm/°C Molded Paper T/R")
      (fields
        (field (name "MANUFACTURER") "Yageo")
        (field (name "MANUFACTURER PART NUMBER") "RC0805FR-07560RL")
      )
      (libsource (lib "clone_Schematic_libary") (part "RC0805FR-07560RL"))
    )
    (comp (ref "R16")
      (value "1M")
      (footprint "R0805")
      (description "SMD Chip Resistor, 1 MOhm, ï¿½ 1%, 125 mW, 0805 [2012 Metric], Thick Film, General Purpose")
      (fields
        (field (name "MANUFACTURER") "Yageo")
        (field (name "MANUFACTURER PART NUMBER") "RC0805FR-071ML")
      )
      (libsource (lib "clone_Schematic_libary") (part "RC0805FR-071ML"))
    )
    (comp (ref "R17")
      (value "560R")
      (footprint "R0805")
      (description "Res General Purpose Thick Film 0805 560 Ohm 1% 1/8W ±100ppm/°C Molded Paper T/R")
      (fields
        (field (name "MANUFACTURER") "Yageo")
        (field (name "MANUFACTURER PART NUMBER") "RC0805FR-07560RL")
      )
      (libsource (lib "clone_Schematic_libary") (part "RC0805FR-07560RL"))
    )
    (comp (ref "R18")
      (value "10k")
      (footprint "R0805")
      (description "SMD Chip Resistor, 10 kOhm, ï¿½ 1%, 125 mW, 0805 [2012 Metric], Thick Film, General Purpose")
      (fields
        (field (name "MANUFACTURER") "Yageo")
        (field (name "MANUFACTURER PART NUMBER") "RC0805FR-0710KL")
      )
      (libsource (lib "clone_Schematic_libary") (part "RC0805FR-0710KL"))
    )
    (comp (ref "R19")
      (value "10k")
      (footprint "R0805")
      (description "SMD Chip Resistor, 10 kOhm, ï¿½ 1%, 125 mW, 0805 [2012 Metric], Thick Film, General Purpose")
      (fields
        (field (name "MANUFACTURER") "Yageo")
        (field (name "MANUFACTURER PART NUMBER") "RC0805FR-0710KL")
      )
      (libsource (lib "clone_Schematic_libary") (part "RC0805FR-0710KL"))
    )
    (comp (ref "R20")
      (value "10k")
      (footprint "R0805")
      (description "SMD Chip Resistor, 10 kOhm, ï¿½ 1%, 125 mW, 0805 [2012 Metric], Thick Film, General Purpose")
      (fields
        (field (name "MANUFACTURER") "Yageo")
        (field (name "MANUFACTURER PART NUMBER") "RC0805FR-0710KL")
      )
      (libsource (lib "clone_Schematic_libary") (part "RC0805FR-0710KL"))
    )
    (comp (ref "R21")
      (value "10k")
      (footprint "R0805")
      (description "SMD Chip Resistor, 10 kOhm, ï¿½ 1%, 125 mW, 0805 [2012 Metric], Thick Film, General Purpose")
      (fields
        (field (name "MANUFACTURER") "Yageo")
        (field (name "MANUFACTURER PART NUMBER") "RC0805FR-0710KL")
      )
      (libsource (lib "clone_Schematic_libary") (part "RC0805FR-0710KL"))
    )
    (comp (ref "R22")
      (value "560R")
      (footprint "R0805")
      (description "Res General Purpose Thick Film 0805 560 Ohm 1% 1/8W ±100ppm/°C Molded Paper T/R")
      (fields
        (field (name "MANUFACTURER") "Yageo")
        (field (name "MANUFACTURER PART NUMBER") "RC0805FR-07560RL")
      )
      (libsource (lib "clone_Schematic_libary") (part "RC0805FR-07560RL"))
    )
    (comp (ref "R23")
      (value "22R")
      (footprint "R0805")
      (description "SMD Chip Resistor, 22 Ohm, ± 1%, 125 mW, 0805 [2012 Metric], Thick Film, General Purpose")
      (fields
        (field (name "MANUFACTURER") "Yageo")
        (field (name "MANUFACTURER PART NUMBER") "RC0805FR-0722RL")
      )
      (libsource (lib "clone_Schematic_libary") (part "RC0805FR-0722RL"))
    )
    (comp (ref "R24")
      (value "22R")
      (footprint "R0805")
      (description "SMD Chip Resistor, 22 Ohm, ± 1%, 125 mW, 0805 [2012 Metric], Thick Film, General Purpose")
      (fields
        (field (name "MANUFACTURER") "Yageo")
        (field (name "MANUFACTURER PART NUMBER") "RC0805FR-0722RL")
      )
      (libsource (lib "clone_Schematic_libary") (part "RC0805FR-0722RL"))
    )
    (comp (ref "R25")
      (value "22R")
      (footprint "R0805")
      (description "SMD Chip Resistor, 22 Ohm, ± 1%, 125 mW, 0805 [2012 Metric], Thick Film, General Purpose")
      (fields
        (field (name "MANUFACTURER") "Yageo")
        (field (name "MANUFACTURER PART NUMBER") "RC0805FR-0722RL")
      )
      (libsource (lib "clone_Schematic_libary") (part "RC0805FR-0722RL"))
    )
    (comp (ref "R26")
      (value "0R")
      (footprint "R0805")
      (libsource (lib "clone_Schematic_libary") (part "0Ohm Resistor"))
    )
    (comp (ref "R27")
      (value "0R")
      (footprint "R0805")
      (libsource (lib "clone_Schematic_libary") (part "0Ohm Resistor"))
    )
    (comp (ref "R28")
      (value "0R")
      (footprint "R0805")
      (libsource (lib "clone_Schematic_libary") (part "0Ohm Resistor"))
    )
    (comp (ref "SCKT FOR U1")
      (value "28-DIP Socket")
      (footprint "28_DIP_SOCKET")
      (description "Socket DIP 28Cnts DualWipe 0.3InSpc. PhosphorBronze Nickel KinkedTail 4800Series ¦ 3M 4828-3004-CP")
      (fields (field (name "MANUFACTURER") "3M") (field (name "MANUFACTURER PART NUMBER") "4828-3004-CP"))
      (libsource (lib "clone_Schematic_libary") (part "4828-3004-CP"))
    )
    (comp (ref "SW1")
      (value "1825910-6")
      (footprint "SW")
      (fields
        (field (name "MANUFACTURER") "TE Connectivity AMP")
        (field (name "MANUFACTURER PART NUMBER") "2-1825910-6")
      )
      (libsource (lib "clone_Schematic_libary") (part "2-1825910-6"))
    )
    (comp (ref "SW2")
      (value "1825910-6")
      (footprint "SW")
      (fields
        (field (name "MANUFACTURER") "TE Connectivity AMP")
        (field (name "MANUFACTURER PART NUMBER") "2-1825910-6")
      )
      (libsource (lib "clone_Schematic_libary") (part "2-1825910-6"))
    )
    (comp (ref "U1")
      (value "ATMEGA328P-PU")
      (footprint "DIP28_MCU")
      (description "Microchip - ATMEGA328P-PU - Microcontroller Mcu, 8 Bit, Atmega, 20MHZ, DIP-28")
      (fields (field (name "MANUFACTURER") "Microchip"))
      (libsource (lib "clone_Schematic_libary") (part "ATMEGA328P-PU"))
    )
    (comp (ref "U2")
      (value "ATMEGA16U2-AU")
      (footprint "TQFP32")
      (description "Risc Microcontroller, 8-BIT, Flash, AVR Risc Cpu, 16MHZ, Cmos, PQFP32")
      (fields
        (field (name "MANUFACTURER") "Microchip")
        (field (name "MANUFACTURER PART NUMBER") "ATMEGA16U2-AUR")
      )
      (libsource (lib "clone_Schematic_libary") (part "ATMEGA16U2-AUR"))
    )
    (comp (ref "U3")
      (value "TL1963A-33DCQR")
      (footprint "VoltageRegulatorSOP")
      (description "LDO Regulator Pos 3.3V 1.5A 6-Pin(5+Tab) SOT-223 T/R")
      (fields (field (name "MANUFACTURER") "Texas Instruments"))
      (libsource (lib "clone_Schematic_libary") (part "TL1963A-33DCQR"))
    )
    (comp (ref "U4")
      (value "SN74AHC1G09DBVR")
      (footprint "DBVSOT23")
      (description "1-ch, 2-input 2-V to 5.5-V high-speed (9 ns) AND gate with open-drain outputs 5-SOT-23 -55 to 125")
      (fields (field (name "MANUFACTURER") "Texas Instruments"))
      (libsource (lib "clone_Schematic_libary") (part "SN74AHC1G09DBVR"))
    )
    (comp (ref "U5")
      (value "SN74AHC1G09DBVR")
      (footprint "DBVSOT23")
      (description "1-ch, 2-input 2-V to 5.5-V high-speed (9 ns) AND gate with open-drain outputs 5-SOT-23 -55 to 125")
      (fields (field (name "MANUFACTURER") "Texas Instruments"))
      (libsource (lib "clone_Schematic_libary") (part "SN74AHC1G09DBVR"))
    )
    (comp (ref "U6")
      (value "SN74AHC1G09DBVR")
      (footprint "DBVSOT23")
      (description "1-ch, 2-input 2-V to 5.5-V high-speed (9 ns) AND gate with open-drain outputs 5-SOT-23 -55 to 125")
      (fields (field (name "MANUFACTURER") "Texas Instruments"))
      (libsource (lib "clone_Schematic_libary") (part "SN74AHC1G09DBVR"))
    )
    (comp (ref "U7")
      (value "SN74AHC1G09DBVR")
      (footprint "DBVSOT23")
      (description "1-ch, 2-input 2-V to 5.5-V high-speed (9 ns) AND gate with open-drain outputs 5-SOT-23 -55 to 125")
      (fields (field (name "MANUFACTURER") "Texas Instruments"))
      (libsource (lib "clone_Schematic_libary") (part "SN74AHC1G09DBVR"))
    )
    (comp (ref "Y1")
      (value "ABM7-16.000MHZ-D2Y-T")
      (footprint "ABM7-16.000MHZ-D2Y-T")
      (description "Crystal 16MHz ±20ppm (Tol) ±30ppm (Stability) 18pF FUND 50Ohm 2-Pin Mini-CSMD T/R")
      (fields (field (name "MANUFACTURER") "Abracon"))
      (libsource (lib "clone_Schematic_libary") (part "ABM7-16.000MHZ-D2Y-T"))
    )
    (comp (ref "Y2")
      (value "ABM7-16.000MHZ-D2Y-T")
      (footprint "ABM7-16.000MHZ-D2Y-T")
      (description "Crystal 16MHz ±20ppm (Tol) ±30ppm (Stability) 18pF FUND 50Ohm 2-Pin Mini-CSMD T/R")
      (fields (field (name "MANUFACTURER") "Abracon"))
      (libsource (lib "clone_Schematic_libary") (part "ABM7-16.000MHZ-D2Y-T"))
    )
    (comp (ref "Z1")
      (value "CG0603MLC-05E")
      (footprint "R0603")
      (description "ESD Suppressor Multilayer Varistor 5V Automotive 2-Pin Case 0603(1608Metric) T/R")
      (fields (field (name "MANUFACTURER") "Bourns") (field (name "VOLTAGE") "5V"))
      (libsource (lib "clone_Schematic_libary") (part "CG0603MLC-05E"))
    )
    (comp (ref "Z2")
      (value "CG0603MLC-05E")
      (footprint "R0603")
      (description "ESD Suppressor Multilayer Varistor 5V Automotive 2-Pin Case 0603(1608Metric) T/R")
      (fields (field (name "MANUFACTURER") "Bourns") (field (name "VOLTAGE") "5V"))
      (libsource (lib "clone_Schematic_libary") (part "CG0603MLC-05E"))
    )
  )
  (nets
    (net (code "1") (name "+3V3") (class "Default")
      (node (ref "C13") (pin "2") (pinfunction "2_2") (pintype "passive"))
      (node (ref "C16") (pin "2") (pinfunction "2_2") (pintype "passive"))
      (node (ref "J1") (pin "4") (pinfunction "4_4") (pintype "passive"))
      (node (ref "JP4") (pin "3") (pinfunction "3_3") (pintype "passive"))
      (node (ref "R28") (pin "2") (pinfunction "2_2") (pintype "passive"))
      (node (ref "U3") (pin "4") (pinfunction "OUT_4") (pintype "passive"))
      (node (ref "U3") (pin "5") (pinfunction "SENSE_5") (pintype "passive"))
    )
    (net (code "2") (name "+5V") (class "Default")
      (node (ref "C12") (pin "2") (pinfunction "2_2") (pintype "passive"))
      (node (ref "C14") (pin "2") (pinfunction "2_2") (pintype "passive"))
      (node (ref "C2") (pin "1") (pinfunction "1_1") (pintype "passive"))
      (node (ref "C6") (pin "2") (pinfunction "2_2") (pintype "passive"))
      (node (ref "J1") (pin "5") (pinfunction "5_5") (pintype "passive"))
      (node (ref "J8") (pin "1") (pinfunction "1_1") (pintype "passive"))
      (node (ref "JP4") (pin "1") (pinfunction "1_1") (pintype "passive"))
      (node (ref "L1") (pin "2") (pinfunction "2_2") (pintype "passive"))
      (node (ref "R27") (pin "1") (pinfunction "1_1") (pintype "passive"))
      (node (ref "U2") (pin "31") (pinfunction "UVCC_31") (pintype "passive"))
      (node (ref "U3") (pin "1") (pinfunction "~{SHDN}_1") (pintype "passive"))
      (node (ref "U3") (pin "2") (pinfunction "IN_2") (pintype "passive"))
    )
    (net (code "3") (name "+5V{slash}3V3") (class "Default")
      (node (ref "C15") (pin "2") (pinfunction "2_2") (pintype "passive"))
      (node (ref "C17") (pin "2") (pinfunction "2_2") (pintype "passive"))
      (node (ref "C26") (pin "2") (pinfunction "2_2") (pintype "passive"))
      (node (ref "C28") (pin "2") (pinfunction "2_2") (pintype "passive"))
      (node (ref "C29") (pin "2") (pinfunction "2_2") (pintype "passive"))
      (node (ref "C30") (pin "2") (pinfunction "2_2") (pintype "passive"))
      (node (ref "C34") (pin "2") (pinfunction "2_2") (pintype "passive"))
      (node (ref "C8") (pin "2") (pinfunction "2_2") (pintype "passive"))
      (node (ref "D5") (pin "1") (pinfunction "Cathode_1") (pintype "passive"))
      (node (ref "D6") (pin "1") (pinfunction "Cathode_1") (pintype "passive"))
      (node (ref "FB1") (pin "1") (pinfunction "1_1") (pintype "passive"))
      (node (ref "FB2") (pin "1") (pinfunction "1_1") (pintype "passive"))
      (node (ref "FB3") (pin "1") (pinfunction "1_1") (pintype "passive"))
      (node (ref "J1") (pin "2") (pinfunction "2_2") (pintype "passive"))
      (node (ref "J5") (pin "2") (pinfunction "2_2") (pintype "passive"))
      (node (ref "J6") (pin "2") (pinfunction "2_2") (pintype "passive"))
      (node (ref "JP4") (pin "2") (pinfunction "2_2") (pintype "passive"))
      (node (ref "R1") (pin "2") (pinfunction "2_2") (pintype "passive"))
      (node (ref "R14") (pin "2") (pinfunction "2_2") (pintype "passive"))
      (node (ref "R15") (pin "2") (pinfunction "2_2") (pintype "passive"))
      (node (ref "R17") (pin "2") (pinfunction "2_2") (pintype "passive"))
      (node (ref "R18") (pin "2") (pinfunction "2_2") (pintype "passive"))
      (node (ref "R19") (pin "2") (pinfunction "2_2") (pintype "passive"))
      (node (ref "R2") (pin "2") (pinfunction "2_2") (pintype "passive"))
      (node (ref "R20") (pin "2") (pinfunction "2_2") (pintype "passive"))
      (node (ref "R21") (pin "2") (pinfunction "2_2") (pintype "passive"))
      (node (ref "R27") (pin "2") (pinfunction "2_2") (pintype "passive"))
      (node (ref "R28") (pin "1") (pinfunction "1_1") (pintype "passive"))
      (node (ref "R3") (pin "2") (pinfunction "2_2") (pintype "passive"))
      (node (ref "R4") (pin "2") (pinfunction "2_2") (pintype "passive"))
      (node (ref "U4") (pin "5") (pinfunction "5_5") (pintype "passive"))
      (node (ref "U5") (pin "5") (pinfunction "5_5") (pintype "passive"))
      (node (ref "U6") (pin "5") (pinfunction "5_5") (pintype "passive"))
      (node (ref "U7") (pin "5") (pinfunction "5_5") (pintype "passive"))
    )
    (net (code "4") (name "+AREF") (class "Default")
      (node (ref "C21") (pin "2") (pinfunction "2_2") (pintype "passive"))
      (node (ref "C24") (pin "2") (pinfunction "2_2") (pintype "passive"))
      (node (ref "J4") (pin "8") (pinfunction "8_8") (pintype "passive"))
      (node (ref "U1") (pin "21") (pinfunction "AREF_21") (pintype "passive"))
    )
    (net (code "5") (name "/+3V3_16U2_UCAP") (class "Default")
      (node (ref "C7") (pin "2") (pinfunction "2_2") (pintype "passive"))
      (node (ref "R26") (pin "1") (pinfunction "1_1") (pintype "passive"))
      (node (ref "U2") (pin "27") (pinfunction "UCAP_27") (pintype "passive"))
    )
    (net (code "6") (name "/+5V_USB") (class "Default")
      (node (ref "C1") (pin "1") (pinfunction "1_1") (pintype "passive"))
      (node (ref "J7") (pin "1") (pinfunction "1_1") (pintype "passive"))
      (node (ref "L1") (pin "1") (pinfunction "1_1") (pintype "passive"))
    )
    (net (code "7") (name "/+5V{slash}3V3_16U2") (class "Default")
      (node (ref "C3") (pin "2") (pinfunction "2_2") (pintype "passive"))
      (node (ref "C4") (pin "2") (pinfunction "2_2") (pintype "passive"))
      (node (ref "C5") (pin "2") (pinfunction "2_2") (pintype "passive"))
      (node (ref "FB1") (pin "2") (pinfunction "2_2") (pintype "passive"))
      (node (ref "R26") (pin "2") (pinfunction "2_2") (pintype "passive"))
      (node (ref "U2") (pin "32") (pinfunction "AVCC_32") (pintype "passive"))
      (node (ref "U2") (pin "4") (pinfunction "VCC_4") (pintype "passive"))
    )
    (net (code "8") (name "/+5V{slash}3V3_328P_AVCC") (class "Default")
      (node (ref "C22") (pin "2") (pinfunction "2_2") (pintype "passive"))
      (node (ref "C23") (pin "2") (pinfunction "2_2") (pintype "passive"))
      (node (ref "FB3") (pin "2") (pinfunction "2_2") (pintype "passive"))
      (node (ref "U1") (pin "20") (pinfunction "AVCC_20") (pintype "passive"))
    )
    (net (code "9") (name "/+5V{slash}3V3_328P_VCC") (class "Default")
      (node (ref "C19") (pin "2") (pinfunction "2_2") (pintype "passive"))
      (node (ref "C20") (pin "2") (pinfunction "2_2") (pintype "passive"))
      (node (ref "FB2") (pin "2") (pinfunction "2_2") (pintype "passive"))
      (node (ref "U1") (pin "7") (pinfunction "VCC_7") (pintype "passive"))
    )
    (net (code "10") (name "/16U2PROG_328P_RESETn") (class "Default")
      (node (ref "JP1") (pin "2") (pinfunction "2_2") (pintype "passive"))
      (node (ref "R1") (pin "1") (pinfunction "1_1") (pintype "passive"))
      (node (ref "U2") (pin "13") (pinfunction "(/_HWB_/_AIN6_/_T0_/_INT7)_PD7_13") (pintype "passive"))
    )
    (net (code "11") (name "/16U2_16MHZ_XTAL1") (class "Default")
      (node (ref "C10") (pin "1") (pinfunction "1_1") (pintype "passive"))
      (node (ref "R9") (pin "2") (pinfunction "2_2") (pintype "passive"))
      (node (ref "U2") (pin "1") (pinfunction "XTAL1_1") (pintype "passive"))
      (node (ref "Y2") (pin "2") (pinfunction "2_2") (pintype "passive"))
    )
    (net (code "12") (name "/16U2_16MHZ_XTAL2") (class "Default")
      (node (ref "C9") (pin "1") (pinfunction "1_1") (pintype "passive"))
      (node (ref "R9") (pin "1") (pinfunction "1_1") (pintype "passive"))
      (node (ref "U2") (pin "2") (pinfunction "(PC0)_XTAL2_2") (pintype "passive"))
      (node (ref "Y2") (pin "1") (pinfunction "1_1") (pintype "passive"))
    )
    (net (code "13") (name "/16U2_BUF_RESETn") (class "Default")
      (node (ref "C31") (pin "2") (pinfunction "2_2") (pintype "passive"))
      (node (ref "R23") (pin "2") (pinfunction "2_2") (pintype "passive"))
      (node (ref "U5") (pin "1") (pinfunction "1_1") (pintype "passive"))
      (node (ref "U5") (pin "2") (pinfunction "2_2") (pintype "passive"))
    )
    (net (code "14") (name "/16U2_HDR_RESETn") (class "Default")
      (node (ref "J6") (pin "5") (pinfunction "5_5") (pintype "passive"))
      (node (ref "JP3") (pin "3") (pinfunction "3_3") (pintype "passive"))
    )
    (net (code "15") (name "/16U2_MISO") (class "Default")
      (node (ref "J6") (pin "1") (pinfunction "1_1") (pintype "passive"))
      (node (ref "U2") (pin "17") (pinfunction "PB3_(PDO_/_MISO_/_PCINT3)_17") (pintype "passive"))
    )
    (net (code "16") (name "/16U2_MOSI") (class "Default")
      (node (ref "J6") (pin "4") (pinfunction "4_4") (pintype "passive"))
      (node (ref "U2") (pin "16") (pinfunction "(PDI_/_MOSI_/_PCINT2)_PB2_16") (pintype "passive"))
    )
    (net (code "17") (name "/16U2_PB4") (class "Default")
      (node (ref "JP2") (pin "1") (pinfunction "1_1") (pintype "passive"))
      (node (ref "JP3") (pin "2") (pinfunction "2_2") (pintype "passive"))
      (node (ref "U2") (pin "18") (pinfunction "PB4_(T1_/_PCINT4)_18") (pintype "passive"))
    )
    (net (code "18") (name "/16U2_PB5") (class "Default")
      (node (ref "JP2") (pin "3") (pinfunction "3_3") (pintype "passive"))
      (node (ref "U2") (pin "19") (pinfunction "PB5_(PCINT5)_19") (pintype "passive"))
    )
    (net (code "19") (name "/16U2_PB6") (class "Default")
      (node (ref "JP2") (pin "2") (pinfunction "2_2") (pintype "passive"))
      (node (ref "U2") (pin "20") (pinfunction "PB6_(PCINT6)_20") (pintype "passive"))
    )
    (net (code "20") (name "/16U2_PB7") (class "Default")
      (node (ref "JP2") (pin "4") (pinfunction "4_4") (pintype "passive"))
      (node (ref "U2") (pin "21") (pinfunction "PB7_(PCINT7_/_OC.0A_/_OC.1C)_21") (pintype "passive"))
    )
    (net (code "21") (name "/16U2_RESETn") (class "Default")
      (node (ref "JP3") (pin "4") (pinfunction "4_4") (pintype "passive"))
      (node (ref "R4") (pin "1") (pinfunction "1_1") (pintype "passive"))
      (node (ref "U2") (pin "24") (pinfunction "~{Reset}_(PC1_/_dW)_24") (pintype "passive"))
      (node (ref "U5") (pin "4") (pinfunction "4_4") (pintype "passive"))
    )
    (net (code "22") (name "/16U2_RXD") (class "Default")
      (node (ref "R11") (pin "1") (pinfunction "1_1") (pintype "passive"))
      (node (ref "U2") (pin "8") (pinfunction "(RXD1_/_AIN1_/_INT2)_PD2_8") (pintype "passive"))
    )
    (net (code "23") (name "/16U2_RX_LED") (class "Default")
      (node (ref "D3") (pin "1") (pinfunction "Cathode_1") (pintype "passive"))
      (node (ref "U2") (pin "10") (pinfunction "(INT5/_AIN3)_PD4_10") (pintype "passive"))
    )
    (net (code "24") (name "/16U2_SCLK") (class "Default")
      (node (ref "J6") (pin "3") (pinfunction "3_3") (pintype "passive"))
      (node (ref "R5") (pin "2") (pinfunction "2_2") (pintype "passive"))
    )
    (net (code "25") (name "/16U2_SCLK_R") (class "Default")
      (node (ref "R5") (pin "1") (pinfunction "1_1") (pintype "passive"))
      (node (ref "U2") (pin "15") (pinfunction "(SCLK_/_PCINT1)_PB1_15") (pintype "passive"))
    )
    (net (code "26") (name "/16U2_TXD") (class "Default")
      (node (ref "R10") (pin "1") (pinfunction "1_1") (pintype "passive"))
      (node (ref "U2") (pin "9") (pinfunction "(TXD1_/_INT3)_PD3_9") (pintype "passive"))
    )
    (net (code "27") (name "/16U2_TX_LED") (class "Default")
      (node (ref "D4") (pin "1") (pinfunction "Cathode_1") (pintype "passive"))
      (node (ref "U2") (pin "11") (pinfunction "(XCK_AIN4_/_PCINT12)_PD5_11") (pintype "passive"))
    )
    (net (code "28") (name "/328P_16MHZ_XTAL1") (class "Default")
      (node (ref "C27") (pin "1") (pinfunction "1_1") (pintype "passive"))
      (node (ref "R16") (pin "2") (pinfunction "2_2") (pintype "passive"))
      (node (ref "U1") (pin "9") (pinfunction "(PCINT6/XTAL1/TOSC1)_PB6_9") (pintype "passive"))
      (node (ref "Y1") (pin "2") (pinfunction "2_2") (pintype "passive"))
    )
    (net (code "29") (name "/328P_16MHZ_XTAL2") (class "Default")
      (node (ref "C25") (pin "1") (pinfunction "1_1") (pintype "passive"))
      (node (ref "R16") (pin "1") (pinfunction "1_1") (pintype "passive"))
      (node (ref "U1") (pin "10") (pinfunction "(PCINT7/XTAL2/TOSC2)_PB7_10") (pintype "passive"))
      (node (ref "Y1") (pin "1") (pinfunction "1_1") (pintype "passive"))
    )
    (net (code "30") (name "/328P_AUTORESETn") (class "Default")
      (node (ref "C11") (pin "2") (pinfunction "2_2") (pintype "passive"))
      (node (ref "R18") (pin "1") (pinfunction "1_1") (pintype "passive"))
      (node (ref "U6") (pin "1") (pinfunction "1_1") (pintype "passive"))
    )
    (net (code "31") (name "/328P_BUF_RESETn") (class "Default")
      (node (ref "C32") (pin "2") (pinfunction "2_2") (pintype "passive"))
      (node (ref "R24") (pin "2") (pinfunction "2_2") (pintype "passive"))
      (node (ref "U6") (pin "2") (pinfunction "2_2") (pintype "passive"))
    )
    (net (code "32") (name "/328P_RESETn") (class "Default")
      (node (ref "J1") (pin "3") (pinfunction "3_3") (pintype "passive"))
      (node (ref "J5") (pin "5") (pinfunction "5_5") (pintype "passive"))
      (node (ref "JP3") (pin "1") (pinfunction "1_1") (pintype "passive"))
      (node (ref "R14") (pin "1") (pinfunction "1_1") (pintype "passive"))
      (node (ref "U1") (pin "1") (pinfunction "(PCINT14/~{RESET})_PC6_1") (pintype "passive"))
      (node (ref "U6") (pin "4") (pinfunction "4_4") (pintype "passive"))
    )
    (net (code "33") (name "/AD0") (class "Default")
      (node (ref "J2") (pin "1") (pinfunction "1_1") (pintype "passive"))
      (node (ref "U1") (pin "23") (pinfunction "PC0_(ADC0/PCINT8)_23") (pintype "passive"))
    )
    (net (code "34") (name "/AD1") (class "Default")
      (node (ref "J2") (pin "2") (pinfunction "2_2") (pintype "passive"))
      (node (ref "U1") (pin "24") (pinfunction "PC1_(ADC1/PCINT9)_24") (pintype "passive"))
    )
    (net (code "35") (name "/AD2") (class "Default")
      (node (ref "J2") (pin "3") (pinfunction "3_3") (pintype "passive"))
      (node (ref "U1") (pin "25") (pinfunction "PC2_(ADC2/PCINT10)_25") (pintype "passive"))
    )
    (net (code "36") (name "/AD3") (class "Default")
      (node (ref "J2") (pin "4") (pinfunction "4_4") (pintype "passive"))
      (node (ref "U1") (pin "26") (pinfunction "PC3_(ADC3/PCINT11)_26") (pintype "passive"))
    )
    (net (code "37") (name "/AD4{slash}SDA") (class "Default")
      (node (ref "J2") (pin "5") (pinfunction "5_5") (pintype "passive"))
      (node (ref "J4") (pin "9") (pinfunction "9_9") (pintype "passive"))
      (node (ref "U1") (pin "27") (pinfunction "PC4_(ADC4/SDA/PCINT12)_27") (pintype "passive"))
    )
    (net (code "38") (name "/AD5{slash}SCL") (class "Default")
      (node (ref "J2") (pin "6") (pinfunction "6_6") (pintype "passive"))
      (node (ref "J4") (pin "10") (pinfunction "10_10") (pintype "passive"))
      (node (ref "U1") (pin "28") (pinfunction "PC5_(ADC5/SCL/PCINT13)_28") (pintype "passive"))
    )
    (net (code "39") (name "/BUTTON_RESETn") (class "Default")
      (node (ref "D6") (pin "2") (pinfunction "Anode_2") (pintype "passive"))
      (node (ref "R20") (pin "1") (pinfunction "1_1") (pintype "passive"))
      (node (ref "R24") (pin "1") (pinfunction "1_1") (pintype "passive"))
      (node (ref "SW1") (pin "3") (pinfunction "3_3") (pintype "passive"))
      (node (ref "SW1") (pin "4") (pinfunction "4_4") (pintype "passive"))
    )
    (net (code "40") (name "/CON_USB_N") (class "Default")
      (node (ref "J7") (pin "2") (pinfunction "2_2") (pintype "passive"))
      (node (ref "R6") (pin "1") (pinfunction "1_1") (pintype "passive"))
      (node (ref "Z1") (pin "2") (pinfunction "2_2") (pintype "passive"))
    )
    (net (code "41") (name "/CON_USB_P") (class "Default")
      (node (ref "J7") (pin "3") (pinfunction "3_3") (pintype "passive"))
      (node (ref "R7") (pin "1") (pinfunction "1_1") (pintype "passive"))
      (node (ref "Z2") (pin "2") (pinfunction "2_2") (pintype "passive"))
    )
    (net (code "42") (name "/D+") (class "Default")
      (node (ref "R7") (pin "2") (pinfunction "2_2") (pintype "passive"))
      (node (ref "U2") (pin "29") (pinfunction "D+_29") (pintype "passive"))
    )
    (net (code "43") (name "/D-") (class "Default")
      (node (ref "R6") (pin "2") (pinfunction "2_2") (pintype "passive"))
      (node (ref "U2") (pin "30") (pinfunction "D-_30") (pintype "passive"))
    )
    (net (code "44") (name "/IO0") (class "Default")
      (node (ref "J3") (pin "1") (pinfunction "1_1") (pintype "passive"))
      (node (ref "R10") (pin "2") (pinfunction "2_2") (pintype "passive"))
      (node (ref "U1") (pin "2") (pinfunction "(PCINT16/RXD)_PD0_2") (pintype "passive"))
    )
    (net (code "45") (name "/IO1") (class "Default")
      (node (ref "J3") (pin "2") (pinfunction "2_2") (pintype "passive"))
      (node (ref "R11") (pin "2") (pinfunction "2_2") (pintype "passive"))
      (node (ref "U1") (pin "3") (pinfunction "(PCINT17/TXD)_PD1_3") (pintype "passive"))
    )
    (net (code "46") (name "/IO2") (class "Default")
      (node (ref "J3") (pin "3") (pinfunction "3_3") (pintype "passive"))
      (node (ref "U1") (pin "4") (pinfunction "(PCINT18/INT0)_PD2_4") (pintype "passive"))
    )
    (net (code "47") (name "/IO3") (class "Default")
      (node (ref "J3") (pin "4") (pinfunction "4_4") (pintype "passive"))
      (node (ref "U1") (pin "5") (pinfunction "(PCINT19/OC2B/INT1)_PD3_5") (pintype "passive"))
    )
    (net (code "48") (name "/IO4") (class "Default")
      (node (ref "J3") (pin "5") (pinfunction "5_5") (pintype "passive"))
      (node (ref "U1") (pin "6") (pinfunction "(PCINT20/XCK/T0)_PD4_6") (pintype "passive"))
    )
    (net (code "49") (name "/IO5") (class "Default")
      (node (ref "J3") (pin "6") (pinfunction "6_6") (pintype "passive"))
      (node (ref "U1") (pin "11") (pinfunction "(PCINT21/OC0B/T1)_PD5_11") (pintype "passive"))
    )
    (net (code "50") (name "/IO6") (class "Default")
      (node (ref "J3") (pin "7") (pinfunction "7_7") (pintype "passive"))
      (node (ref "U1") (pin "12") (pinfunction "(PCINT22/OC0A/AIN0)_PD6_12") (pintype "passive"))
    )
    (net (code "51") (name "/IO7") (class "Default")
      (node (ref "J3") (pin "8") (pinfunction "8_8") (pintype "passive"))
      (node (ref "U1") (pin "13") (pinfunction "(PCINT23/AIN1)_PD7_13") (pintype "passive"))
    )
    (net (code "52") (name "/IO8") (class "Default")
      (node (ref "J4") (pin "1") (pinfunction "1_1") (pintype "passive"))
      (node (ref "R22") (pin "2") (pinfunction "2_2") (pintype "passive"))
      (node (ref "U1") (pin "14") (pinfunction "(PCINT0/CLKO/ICP1)_PB0_14") (pintype "passive"))
    )
    (net (code "53") (name "/IO9") (class "Default")
      (node (ref "J4") (pin "2") (pinfunction "2_2") (pintype "passive"))
      (node (ref "U1") (pin "15") (pinfunction "PB1_(OC1A/PCINT1)_15") (pintype "passive"))
    )
    (net (code "54") (name "/MISO") (class "Default")
      (node (ref "J4") (pin "5") (pinfunction "5_5") (pintype "passive"))
      (node (ref "J5") (pin "1") (pinfunction "1_1") (pintype "passive"))
      (node (ref "U1") (pin "18") (pinfunction "PB4_(MISO/PCINT4)_18") (pintype "passive"))
    )
    (net (code "55") (name "/MOSI") (class "Default")
      (node (ref "J4") (pin "4") (pinfunction "4_4") (pintype "passive"))
      (node (ref "J5") (pin "4") (pinfunction "4_4") (pintype "passive"))
      (node (ref "U1") (pin "17") (pinfunction "PB3_(MOSI/OC2A/PCINT3)_17") (pintype "passive"))
    )
    (net (code "56") (name "/SCK") (class "Default")
      (node (ref "J4") (pin "6") (pinfunction "6_6") (pintype "passive"))
      (node (ref "J5") (pin "3") (pinfunction "3_3") (pintype "passive"))
      (node (ref "R13") (pin "2") (pinfunction "2_2") (pintype "passive"))
      (node (ref "U4") (pin "1") (pinfunction "1_1") (pintype "passive"))
      (node (ref "U4") (pin "2") (pinfunction "2_2") (pintype "passive"))
    )
    (net (code "57") (name "/SCK_R") (class "Default")
      (node (ref "R13") (pin "1") (pinfunction "1_1") (pintype "passive"))
      (node (ref "U1") (pin "19") (pinfunction "PB5_(SCK/PCINT5)_19") (pintype "passive"))
    )
    (net (code "58") (name "/SS") (class "Default")
      (node (ref "J4") (pin "3") (pinfunction "3_3") (pintype "passive"))
      (node (ref "U1") (pin "16") (pinfunction "PB2_(~{SS}/OC1B/PCINT2)_16") (pintype "passive"))
    )
    (net (code "59") (name "/USER_BUTTON") (class "Default")
      (node (ref "R21") (pin "1") (pinfunction "1_1") (pintype "passive"))
      (node (ref "R25") (pin "1") (pinfunction "1_1") (pintype "passive"))
      (node (ref "SW2") (pin "3") (pinfunction "3_3") (pintype "passive"))
      (node (ref "SW2") (pin "4") (pinfunction "4_4") (pintype "passive"))
    )
    (net (code "60") (name "/USER_BUTTON_BUF") (class "Default")
      (node (ref "C33") (pin "2") (pinfunction "2_2") (pintype "passive"))
      (node (ref "R25") (pin "2") (pinfunction "2_2") (pintype "passive"))
      (node (ref "U7") (pin "1") (pinfunction "1_1") (pintype "passive"))
      (node (ref "U7") (pin "2") (pinfunction "2_2") (pintype "passive"))
    )
    (net (code "61") (name "GND") (class "Default")
      (node (ref "C1") (pin "2") (pinfunction "2_2") (pintype "passive"))
      (node (ref "C10") (pin "2") (pinfunction "2_2") (pintype "passive"))
      (node (ref "C12") (pin "1") (pinfunction "1_1") (pintype "passive"))
      (node (ref "C13") (pin "1") (pinfunction "1_1") (pintype "passive"))
      (node (ref "C14") (pin "1") (pinfunction "1_1") (pintype "passive"))
      (node (ref "C15") (pin "1") (pinfunction "1_1") (pintype "passive"))
      (node (ref "C16") (pin "1") (pinfunction "1_1") (pintype "passive"))
      (node (ref "C17") (pin "1") (pinfunction "1_1") (pintype "passive"))
      (node (ref "C19") (pin "1") (pinfunction "1_1") (pintype "passive"))
      (node (ref "C2") (pin "2") (pinfunction "2_2") (pintype "passive"))
      (node (ref "C20") (pin "1") (pinfunction "1_1") (pintype "passive"))
      (node (ref "C21") (pin "1") (pinfunction "1_1") (pintype "passive"))
      (node (ref "C22") (pin "1") (pinfunction "1_1") (pintype "passive"))
      (node (ref "C23") (pin "1") (pinfunction "1_1") (pintype "passive"))
      (node (ref "C24") (pin "1") (pinfunction "1_1") (pintype "passive"))
      (node (ref "C25") (pin "2") (pinfunction "2_2") (pintype "passive"))
      (node (ref "C26") (pin "1") (pinfunction "1_1") (pintype "passive"))
      (node (ref "C27") (pin "2") (pinfunction "2_2") (pintype "passive"))
      (node (ref "C28") (pin "1") (pinfunction "1_1") (pintype "passive"))
      (node (ref "C29") (pin "1") (pinfunction "1_1") (pintype "passive"))
      (node (ref "C3") (pin "1") (pinfunction "1_1") (pintype "passive"))
      (node (ref "C30") (pin "1") (pinfunction "1_1") (pintype "passive"))
      (node (ref "C31") (pin "1") (pinfunction "1_1") (pintype "passive"))
      (node (ref "C32") (pin "1") (pinfunction "1_1") (pintype "passive"))
      (node (ref "C33") (pin "1") (pinfunction "1_1") (pintype "passive"))
      (node (ref "C34") (pin "1") (pinfunction "1_1") (pintype "passive"))
      (node (ref "C4") (pin "1") (pinfunction "1_1") (pintype "passive"))
      (node (ref "C5") (pin "1") (pinfunction "1_1") (pintype "passive"))
      (node (ref "C6") (pin "1") (pinfunction "1_1") (pintype "passive"))
      (node (ref "C7") (pin "1") (pinfunction "1_1") (pintype "passive"))
      (node (ref "C8") (pin "1") (pinfunction "1_1") (pintype "passive"))
      (node (ref "C9") (pin "2") (pinfunction "2_2") (pintype "passive"))
      (node (ref "D1") (pin "1") (pinfunction "Cathode_1") (pintype "passive"))
      (node (ref "J1") (pin "6") (pinfunction "6_6") (pintype "passive"))
      (node (ref "J1") (pin "7") (pinfunction "7_7") (pintype "passive"))
      (node (ref "J4") (pin "7") (pinfunction "7_7") (pintype "passive"))
      (node (ref "J5") (pin "6") (pinfunction "6_6") (pintype "passive"))
      (node (ref "J6") (pin "6") (pinfunction "6_6") (pintype "passive"))
      (node (ref "J7") (pin "10") (pinfunction "10_10") (pintype "passive"))
      (node (ref "J7") (pin "11") (pinfunction "11_11") (pintype "passive"))
      (node (ref "J7") (pin "5") (pinfunction "5_5") (pintype "passive"))
      (node (ref "J7") (pin "6") (pinfunction "6_6") (pintype "passive"))
      (node (ref "J7") (pin "7") (pinfunction "7_7") (pintype "passive"))
      (node (ref "J7") (pin "8") (pinfunction "8_8") (pintype "passive"))
      (node (ref "J7") (pin "9") (pinfunction "9_9") (pintype "passive"))
      (node (ref "J9") (pin "1") (pinfunction "1_1") (pintype "passive"))
      (node (ref "MH1") (pin "1") (pinfunction "1_1") (pintype "passive"))
      (node (ref "MH2") (pin "1") (pinfunction "1_1") (pintype "passive"))
      (node (ref "MH3") (pin "1") (pinfunction "1_1") (pintype "passive"))
      (node (ref "R12") (pin "2") (pinfunction "2_2") (pintype "passive"))
      (node (ref "R8") (pin "2") (pinfunction "2_2") (pintype "passive"))
      (node (ref "SW1") (pin "1") (pinfunction "1_1") (pintype "passive"))
      (node (ref "SW1") (pin "2") (pinfunction "2_2") (pintype "passive"))
      (node (ref "SW2") (pin "1") (pinfunction "1_1") (pintype "passive"))
      (node (ref "SW2") (pin "2") (pinfunction "2_2") (pintype "passive"))
      (node (ref "U1") (pin "22") (pinfunction "GND_22") (pintype "passive"))
      (node (ref "U1") (pin "8") (pinfunction "GND_8") (pintype "passive"))
      (node (ref "U2") (pin "28") (pinfunction "UGND_28") (pintype "passive"))
      (node (ref "U2") (pin "3") (pinfunction "GND_3") (pintype "passive"))
      (node (ref "U3") (pin "3") (pinfunction "GND_3") (pintype "passive"))
      (node (ref "U3") (pin "6") (pinfunction "EPAD_6") (pintype "passive"))
      (node (ref "U4") (pin "3") (pinfunction "3_3") (pintype "passive"))
      (node (ref "U5") (pin "3") (pinfunction "3_3") (pintype "passive"))
      (node (ref "U6") (pin "3") (pinfunction "3_3") (pintype "passive"))
      (node (ref "U7") (pin "3") (pinfunction "3_3") (pintype "passive"))
      (node (ref "Z1") (pin "1") (pinfunction "1_1") (pintype "passive"))
      (node (ref "Z2") (pin "1") (pinfunction "1_1") (pintype "passive"))
    )
    (net (code "62") (name "Net-(C11-Pad1)") (class "Default")
      (node (ref "C11") (pin "1") (pinfunction "1_1") (pintype "passive"))
      (node (ref "JP1") (pin "1") (pinfunction "1_1") (pintype "passive"))
    )
    (net (code "63") (name "Net-(D1-Anode)") (class "Default")
      (node (ref "D1") (pin "2") (pinfunction "Anode_2") (pintype "passive"))
      (node (ref "R17") (pin "1") (pinfunction "1_1") (pintype "passive"))
    )
    (net (code "64") (name "Net-(D2-Anode)") (class "Default")
      (node (ref "D2") (pin "2") (pinfunction "Anode_2") (pintype "passive"))
      (node (ref "R15") (pin "1") (pinfunction "1_1") (pintype "passive"))
    )
    (net (code "65") (name "Net-(D2-Cathode)") (class "Default")
      (node (ref "D2") (pin "1") (pinfunction "Cathode_1") (pintype "passive"))
      (node (ref "U4") (pin "4") (pinfunction "4_4") (pintype "passive"))
    )
    (net (code "66") (name "Net-(D3-Anode)") (class "Default")
      (node (ref "D3") (pin "2") (pinfunction "Anode_2") (pintype "passive"))
      (node (ref "R2") (pin "1") (pinfunction "1_1") (pintype "passive"))
    )
    (net (code "67") (name "Net-(D4-Anode)") (class "Default")
      (node (ref "D4") (pin "2") (pinfunction "Anode_2") (pintype "passive"))
      (node (ref "R3") (pin "1") (pinfunction "1_1") (pintype "passive"))
    )
    (net (code "68") (name "Net-(D5-Anode)") (class "Default")
      (node (ref "D5") (pin "2") (pinfunction "Anode_2") (pintype "passive"))
      (node (ref "R19") (pin "1") (pinfunction "1_1") (pintype "passive"))
      (node (ref "R23") (pin "1") (pinfunction "1_1") (pintype "passive"))
    )
    (net (code "69") (name "Net-(J7-Pad4)") (class "Default")
      (node (ref "J7") (pin "4") (pinfunction "4_4") (pintype "passive"))
      (node (ref "R8") (pin "1") (pinfunction "1_1") (pintype "passive"))
    )
    (net (code "70") (name "Net-(JP1-Pad3)") (class "Default")
      (node (ref "JP1") (pin "3") (pinfunction "3_3") (pintype "passive"))
      (node (ref "R12") (pin "1") (pinfunction "1_1") (pintype "passive"))
    )
    (net (code "71") (name "Net-(R22-Pad1)") (class "Default")
      (node (ref "R22") (pin "1") (pinfunction "1_1") (pintype "passive"))
      (node (ref "U7") (pin "4") (pinfunction "4_4") (pintype "passive"))
    )
    (net (code "72") (name "unconnected-(J1-Pad1)") (class "Default")
      (node (ref "J1") (pin "1") (pinfunction "1_1") (pintype "passive+no_connect"))
    )
    (net (code "73") (name "unconnected-(J1-Pad8)") (class "Default")
      (node (ref "J1") (pin "8") (pinfunction "8_8") (pintype "passive+no_connect"))
    )
    (net (code "74") (name "unconnected-(MH4-Pad1)") (class "Default")
      (node (ref "MH4") (pin "1") (pinfunction "1_1") (pintype "passive+no_connect"))
    )
    (net (code "75") (name "unconnected-(U2-(AIN0_{slash}_INT1)_PD1-Pad7)") (class "Default")
      (node (ref "U2") (pin "7") (pinfunction "(AIN0_/_INT1)_PD1_7") (pintype "passive+no_connect"))
    )
    (net (code "76") (name "unconnected-(U2-(OC.0B_{slash}_INT0)_PD0-Pad6)") (class "Default")
      (node (ref "U2") (pin "6") (pinfunction "(OC.0B_/_INT0)_PD0_6") (pintype "passive+no_connect"))
    )
    (net (code "77") (name "unconnected-(U2-(PCINT11_{slash}AIN2_)_PC2-Pad5)") (class "Default")
      (node (ref "U2") (pin "5") (pinfunction "(PCINT11_/AIN2_)_PC2_5") (pintype "passive+no_connect"))
    )
    (net (code "78") (name "unconnected-(U2-(~{RTS}_{slash}_AIN5_{slash}_INT6)_PD6-Pad12)") (class "Default")
      (node (ref "U2") (pin "12") (pinfunction "(~{RTS}_/_AIN5_/_INT6)_PD6_12") (pintype "passive+no_connect"))
    )
    (net (code "79") (name "unconnected-(U2-(~{SS}_{slash}_PCINT0)_PB0-Pad14)") (class "Default")
      (node (ref "U2") (pin "14") (pinfunction "(~{SS}_/_PCINT0)_PB0_14") (pintype "passive+no_connect"))
    )
    (net (code "80") (name "unconnected-(U2-PC4_(PCINT10)-Pad26)") (class "Default")
      (node (ref "U2") (pin "26") (pinfunction "PC4_(PCINT10)_26") (pintype "passive+no_connect"))
    )
    (net (code "81") (name "unconnected-(U2-PC5_(_PCINT9{slash}_OC.1B)-Pad25)") (class "Default")
      (node (ref "U2") (pin "25") (pinfunction "PC5_(_PCINT9/_OC.1B)_25") (pintype "passive+no_connect"))
    )
    (net (code "82") (name "unconnected-(U2-PC6_(OC.1A_{slash}_PCINT8)-Pad23)") (class "Default")
      (node (ref "U2") (pin "23") (pinfunction "PC6_(OC.1A_/_PCINT8)_23") (pintype "passive+no_connect"))
    )
    (net (code "83") (name "unconnected-(U2-PC7_(INT4_{slash}_ICP1_{slash}_CLKO)-Pad22)") (class "Default")
      (node (ref "U2") (pin "22") (pinfunction "PC7_(INT4_/_ICP1_/_CLKO)_22") (pintype "passive+no_connect"))
    )
  )
)
